# Hive_1_7.net
KiCad netlist of a schematic drawn in EAGLE
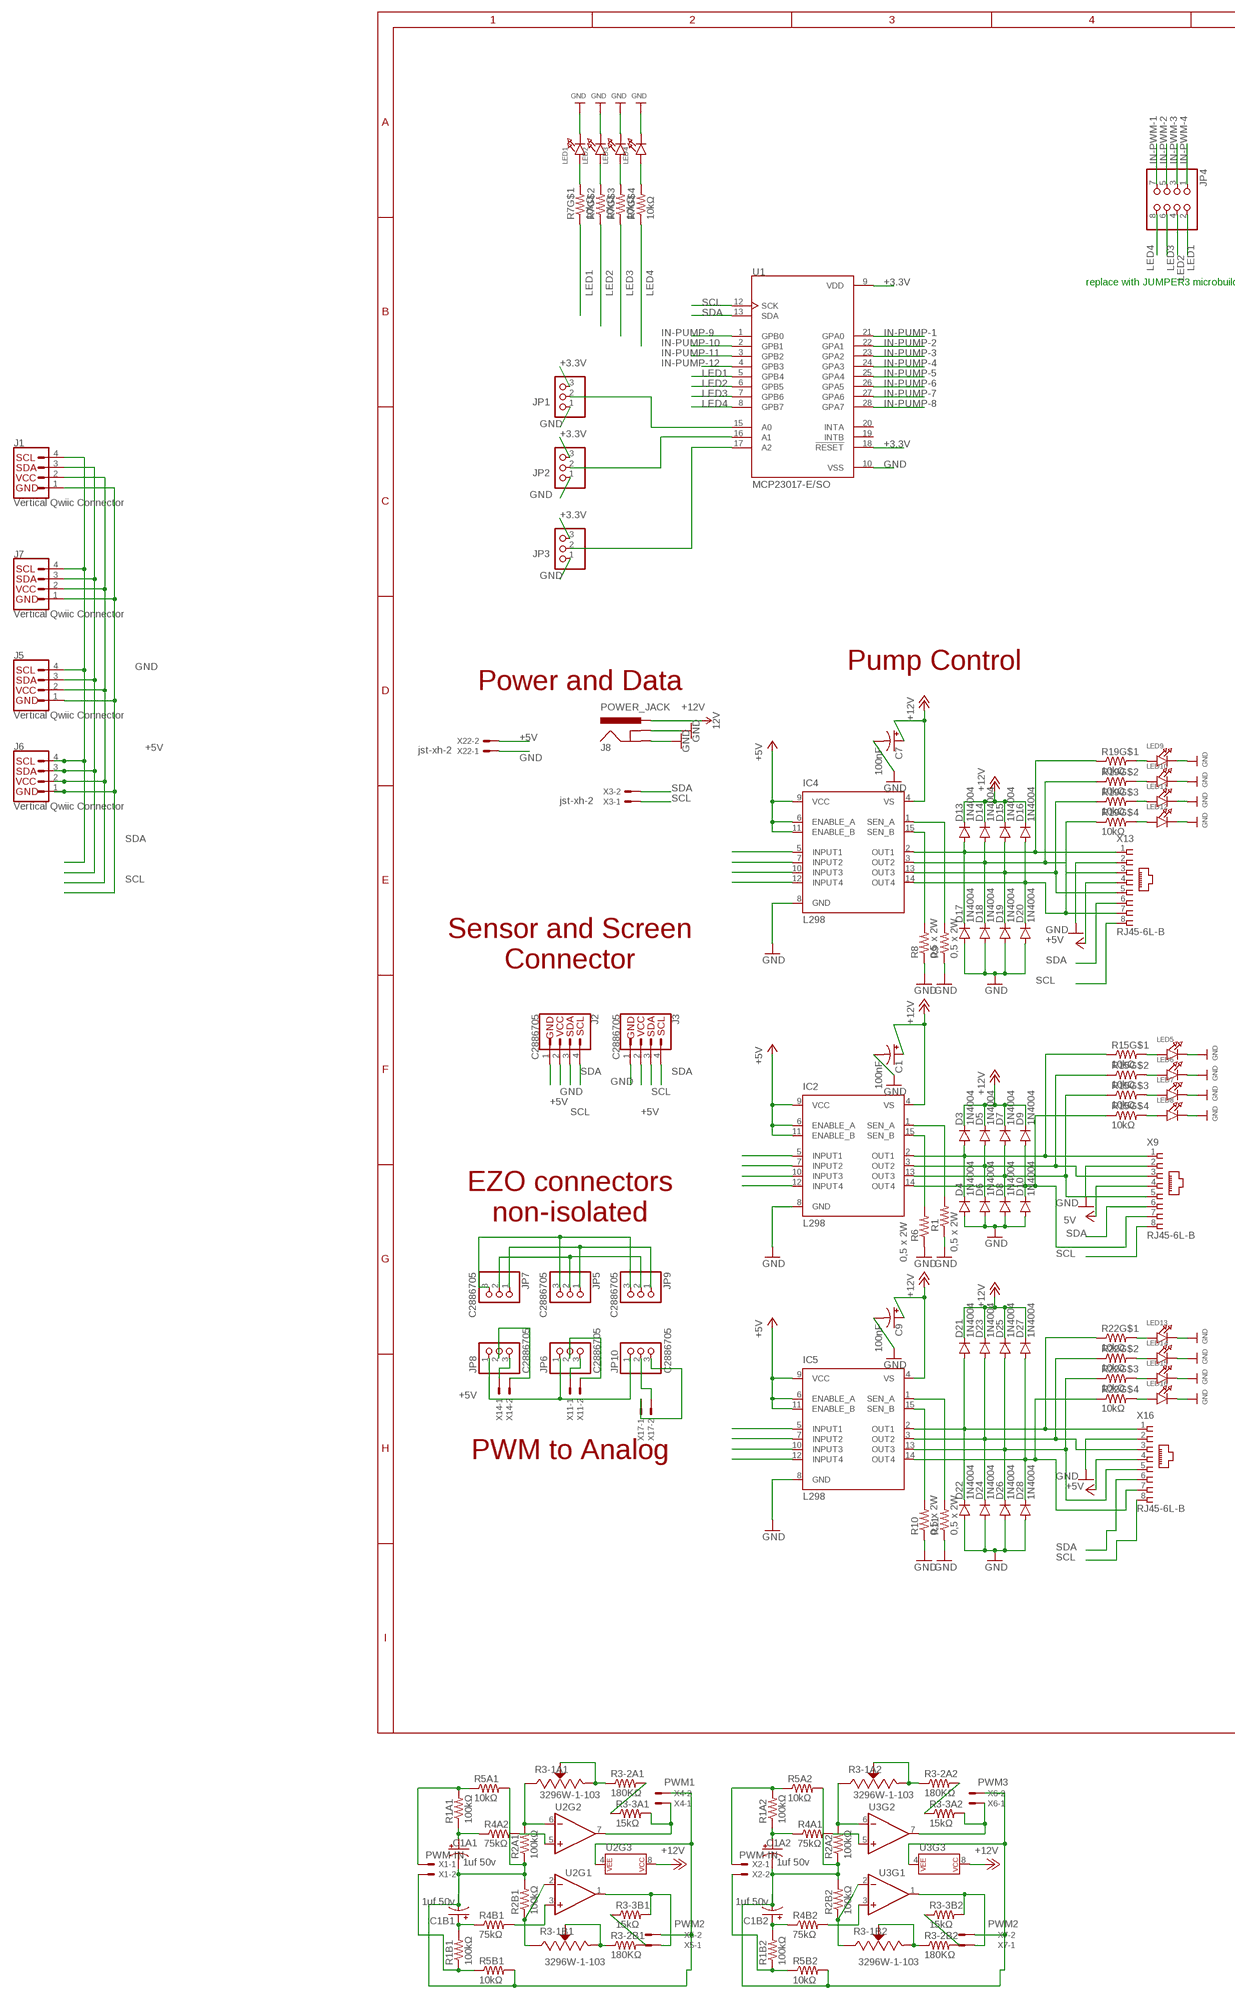
[diagram p0: schematic, sheet 1, part 1 of 2]
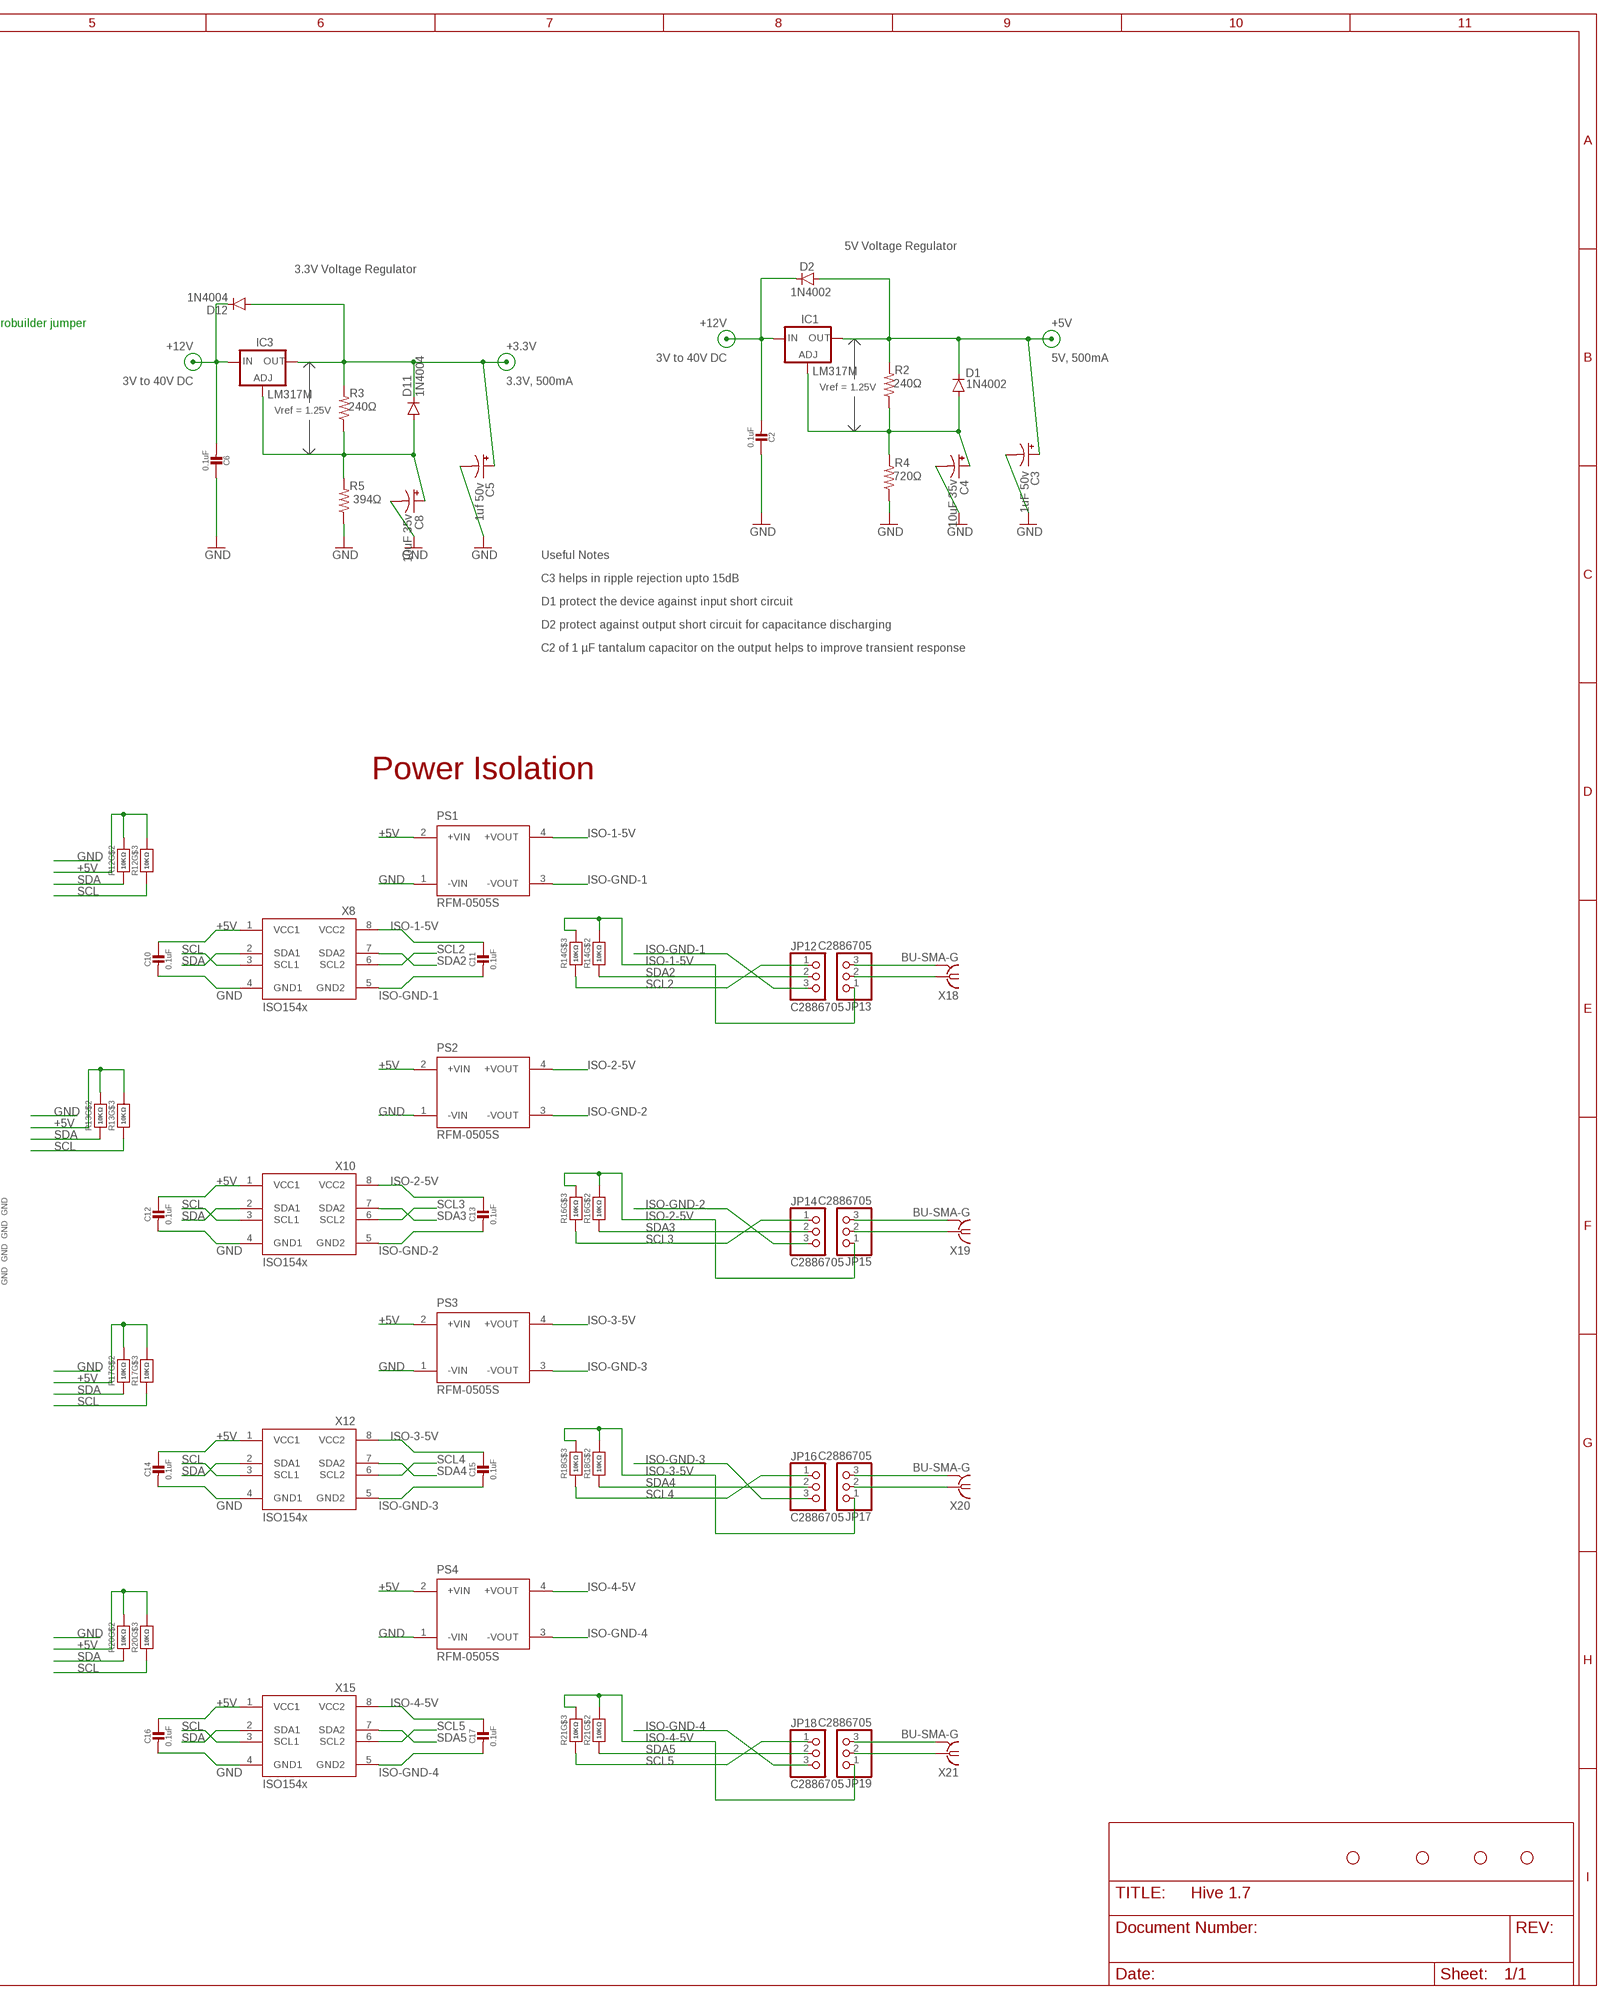
[diagram p1: schematic, sheet 1, part 2 of 2]

(export (version "E")
  (design (tool "Eeschema 10.0.6"))
  (components
    (comp (ref "C1")
      (value "100nF")
      (footprint "eagle-import:UD-4X5,8_NICHICON")
      (libsource (lib "eagle-import") (part "CPOL-USUD-4X5,8"))
    )
    (comp (ref "C1A1")
      (value "1uf 50v")
      (footprint "eagle-import:UD-4X5,8_NICHICON")
      (libsource (lib "eagle-import") (part "CPOL-USUD-4X5,8"))
    )
    (comp (ref "C1A2")
      (value "1uf 50v")
      (footprint "eagle-import:UD-4X5,8_NICHICON")
      (libsource (lib "eagle-import") (part "CPOL-USUD-4X5,8"))
    )
    (comp (ref "C1B1")
      (value "1uf 50v")
      (footprint "eagle-import:UD-4X5,8_NICHICON")
      (libsource (lib "eagle-import") (part "CPOL-USUD-4X5,8"))
    )
    (comp (ref "C1B2")
      (value "1uf 50v")
      (footprint "eagle-import:UD-4X5,8_NICHICON")
      (libsource (lib "eagle-import") (part "CPOL-USUD-4X5,8"))
    )
    (comp (ref "C2")
      (value "0.1uF")
      (footprint "eagle-import:0603-NO")
      (libsource (lib "eagle-import") (part "CAP_CERAMIC0603_NO"))
    )
    (comp (ref "C3")
      (value "1uF 50v")
      (footprint "eagle-import:UD-4X5,8_NICHICON")
      (libsource (lib "eagle-import") (part "CPOL-USUD-4X5,8"))
    )
    (comp (ref "C4")
      (value "10uF 35v")
      (footprint "eagle-import:UD-4X5,8_NICHICON")
      (libsource (lib "eagle-import") (part "CPOL-USUD-4X5,8"))
    )
    (comp (ref "C5")
      (value "1uf 50v")
      (footprint "eagle-import:UD-4X5,8_NICHICON")
      (libsource (lib "eagle-import") (part "CPOL-USUD-4X5,8"))
    )
    (comp (ref "C6")
      (value "0.1uF")
      (footprint "eagle-import:0603-NO")
      (libsource (lib "eagle-import") (part "CAP_CERAMIC0603_NO"))
    )
    (comp (ref "C7")
      (value "100nF")
      (footprint "eagle-import:UD-4X5,8_NICHICON")
      (libsource (lib "eagle-import") (part "CPOL-USUD-4X5,8"))
    )
    (comp (ref "C8")
      (value "10uF 35v")
      (footprint "eagle-import:UD-4X5,8_NICHICON")
      (libsource (lib "eagle-import") (part "CPOL-USUD-4X5,8"))
    )
    (comp (ref "C9")
      (value "100nF")
      (footprint "eagle-import:UD-4X5,8_NICHICON")
      (libsource (lib "eagle-import") (part "CPOL-USUD-4X5,8"))
    )
    (comp (ref "C10")
      (value "0.1uF")
      (footprint "eagle-import:0603-NO")
      (libsource (lib "eagle-import") (part "CAP_CERAMIC0603_NO"))
    )
    (comp (ref "C11")
      (value "0.1uF")
      (footprint "eagle-import:0603-NO")
      (libsource (lib "eagle-import") (part "CAP_CERAMIC0603_NO"))
    )
    (comp (ref "C12")
      (value "0.1uF")
      (footprint "eagle-import:0603-NO")
      (libsource (lib "eagle-import") (part "CAP_CERAMIC0603_NO"))
    )
    (comp (ref "C13")
      (value "0.1uF")
      (footprint "eagle-import:0603-NO")
      (libsource (lib "eagle-import") (part "CAP_CERAMIC0603_NO"))
    )
    (comp (ref "C14")
      (value "0.1uF")
      (footprint "eagle-import:0603-NO")
      (libsource (lib "eagle-import") (part "CAP_CERAMIC0603_NO"))
    )
    (comp (ref "C15")
      (value "0.1uF")
      (footprint "eagle-import:0603-NO")
      (libsource (lib "eagle-import") (part "CAP_CERAMIC0603_NO"))
    )
    (comp (ref "C16")
      (value "0.1uF")
      (footprint "eagle-import:0603-NO")
      (libsource (lib "eagle-import") (part "CAP_CERAMIC0603_NO"))
    )
    (comp (ref "C17")
      (value "0.1uF")
      (footprint "eagle-import:0603-NO")
      (libsource (lib "eagle-import") (part "CAP_CERAMIC0603_NO"))
    )
    (comp (ref "D1")
      (value "1N4002")
      (footprint "eagle-import:DO214BA")
      (libsource (lib "eagle-import") (part "DIODE-DO214BA"))
    )
    (comp (ref "D2")
      (value "1N4002")
      (footprint "eagle-import:DO214BA")
      (libsource (lib "eagle-import") (part "DIODE-DO214BA"))
    )
    (comp (ref "D3")
      (value "1N4004")
      (footprint "eagle-import:DO214BA")
      (libsource (lib "eagle-import") (part "DIODE-DO214BA"))
    )
    (comp (ref "D4")
      (value "1N4004")
      (footprint "eagle-import:DO214BA")
      (libsource (lib "eagle-import") (part "DIODE-DO214BA"))
    )
    (comp (ref "D5")
      (value "1N4004")
      (footprint "eagle-import:DO214BA")
      (libsource (lib "eagle-import") (part "DIODE-DO214BA"))
    )
    (comp (ref "D6")
      (value "1N4004")
      (footprint "eagle-import:DO214BA")
      (libsource (lib "eagle-import") (part "DIODE-DO214BA"))
    )
    (comp (ref "D7")
      (value "1N4004")
      (footprint "eagle-import:DO214BA")
      (libsource (lib "eagle-import") (part "DIODE-DO214BA"))
    )
    (comp (ref "D8")
      (value "1N4004")
      (footprint "eagle-import:DO214BA")
      (libsource (lib "eagle-import") (part "DIODE-DO214BA"))
    )
    (comp (ref "D9")
      (value "1N4004")
      (footprint "eagle-import:DO214BA")
      (libsource (lib "eagle-import") (part "DIODE-DO214BA"))
    )
    (comp (ref "D10")
      (value "1N4004")
      (footprint "eagle-import:DO214BA")
      (libsource (lib "eagle-import") (part "DIODE-DO214BA"))
    )
    (comp (ref "D11")
      (value "1N4004")
      (footprint "eagle-import:DO214BA")
      (libsource (lib "eagle-import") (part "DIODE-DO214BA"))
    )
    (comp (ref "D12")
      (value "1N4004")
      (footprint "eagle-import:DO214BA")
      (libsource (lib "eagle-import") (part "DIODE-DO214BA"))
    )
    (comp (ref "D13")
      (value "1N4004")
      (footprint "eagle-import:DO214BA")
      (libsource (lib "eagle-import") (part "DIODE-DO214BA"))
    )
    (comp (ref "D14")
      (value "1N4004")
      (footprint "eagle-import:DO214BA")
      (libsource (lib "eagle-import") (part "DIODE-DO214BA"))
    )
    (comp (ref "D15")
      (value "1N4004")
      (footprint "eagle-import:DO214BA")
      (libsource (lib "eagle-import") (part "DIODE-DO214BA"))
    )
    (comp (ref "D16")
      (value "1N4004")
      (footprint "eagle-import:DO214BA")
      (libsource (lib "eagle-import") (part "DIODE-DO214BA"))
    )
    (comp (ref "D17")
      (value "1N4004")
      (footprint "eagle-import:DO214BA")
      (libsource (lib "eagle-import") (part "DIODE-DO214BA"))
    )
    (comp (ref "D18")
      (value "1N4004")
      (footprint "eagle-import:DO214BA")
      (libsource (lib "eagle-import") (part "DIODE-DO214BA"))
    )
    (comp (ref "D19")
      (value "1N4004")
      (footprint "eagle-import:DO214BA")
      (libsource (lib "eagle-import") (part "DIODE-DO214BA"))
    )
    (comp (ref "D20")
      (value "1N4004")
      (footprint "eagle-import:DO214BA")
      (libsource (lib "eagle-import") (part "DIODE-DO214BA"))
    )
    (comp (ref "D21")
      (value "1N4004")
      (footprint "eagle-import:DO214BA")
      (libsource (lib "eagle-import") (part "DIODE-DO214BA"))
    )
    (comp (ref "D22")
      (value "1N4004")
      (footprint "eagle-import:DO214BA")
      (libsource (lib "eagle-import") (part "DIODE-DO214BA"))
    )
    (comp (ref "D23")
      (value "1N4004")
      (footprint "eagle-import:DO214BA")
      (libsource (lib "eagle-import") (part "DIODE-DO214BA"))
    )
    (comp (ref "D24")
      (value "1N4004")
      (footprint "eagle-import:DO214BA")
      (libsource (lib "eagle-import") (part "DIODE-DO214BA"))
    )
    (comp (ref "D25")
      (value "1N4004")
      (footprint "eagle-import:DO214BA")
      (libsource (lib "eagle-import") (part "DIODE-DO214BA"))
    )
    (comp (ref "D26")
      (value "1N4004")
      (footprint "eagle-import:DO214BA")
      (libsource (lib "eagle-import") (part "DIODE-DO214BA"))
    )
    (comp (ref "D27")
      (value "1N4004")
      (footprint "eagle-import:DO214BA")
      (libsource (lib "eagle-import") (part "DIODE-DO214BA"))
    )
    (comp (ref "D28")
      (value "1N4004")
      (footprint "eagle-import:DO214BA")
      (libsource (lib "eagle-import") (part "DIODE-DO214BA"))
    )
    (comp (ref "H1")
      (value "STAND-OFF")
      (footprint "eagle-import:STAND-OFF")
      (libsource (lib "eagle-import") (part "STAND-OFF"))
    )
    (comp (ref "H2")
      (value "STAND-OFF")
      (footprint "eagle-import:STAND-OFF")
      (libsource (lib "eagle-import") (part "STAND-OFF"))
    )
    (comp (ref "H3")
      (value "STAND-OFF")
      (footprint "eagle-import:STAND-OFF")
      (libsource (lib "eagle-import") (part "STAND-OFF"))
    )
    (comp (ref "H4")
      (value "STAND-OFF")
      (footprint "eagle-import:STAND-OFF")
      (libsource (lib "eagle-import") (part "STAND-OFF"))
    )
    (comp (ref "IC1")
      (value "LM317MBSTT3")
      (footprint "eagle-import:SOT223")
      (fields (field (name "PARTNUMBER") "LM317M"))
      (libsource (lib "eagle-import") (part "LM317?MBSTT3"))
    )
    (comp (ref "IC2")
      (value "L298")
      (footprint "eagle-import:MULTIWATT-15")
      (fields (field (name "MPN") "L298N"))
      (libsource (lib "eagle-import") (part "L298"))
    )
    (comp (ref "IC3")
      (value "LM317MBSTT3")
      (footprint "eagle-import:SOT223")
      (fields (field (name "PARTNUMBER") "LM317M"))
      (libsource (lib "eagle-import") (part "LM317?MBSTT3"))
    )
    (comp (ref "IC4")
      (value "L298")
      (footprint "eagle-import:MULTIWATT-15")
      (fields (field (name "MPN") "L298N"))
      (libsource (lib "eagle-import") (part "L298"))
    )
    (comp (ref "IC5")
      (value "L298")
      (footprint "eagle-import:MULTIWATT-15")
      (fields (field (name "MPN") "L298N"))
      (libsource (lib "eagle-import") (part "L298"))
    )
    (comp (ref "J1")
      (value "Vertical Qwiic Connector")
      (footprint "eagle-import:JST04_1MM_VERT")
      (libsource (lib "eagle-import") (part "QWIIC_CONNECTOR"))
    )
    (comp (ref "J2")
      (value "C2886705")
      (footprint "eagle-import:1X04")
      (libsource (lib "eagle-import") (part "I2C_STANDARD"))
    )
    (comp (ref "J3")
      (value "C2886705")
      (footprint "eagle-import:1X04")
      (libsource (lib "eagle-import") (part "I2C_STANDARD"))
    )
    (comp (ref "J5")
      (value "Vertical Qwiic Connector")
      (footprint "eagle-import:JST04_1MM_VERT")
      (libsource (lib "eagle-import") (part "QWIIC_CONNECTOR"))
    )
    (comp (ref "J6")
      (value "Vertical Qwiic Connector")
      (footprint "eagle-import:JST04_1MM_VERT")
      (libsource (lib "eagle-import") (part "QWIIC_CONNECTOR"))
    )
    (comp (ref "J7")
      (value "Vertical Qwiic Connector")
      (footprint "eagle-import:JST04_1MM_VERT")
      (libsource (lib "eagle-import") (part "QWIIC_CONNECTOR"))
    )
    (comp (ref "J8")
      (value "POWER_JACK")
      (footprint "eagle-import:POWER_JACK_PTH")
      (libsource (lib "eagle-import") (part "POWER_JACK"))
    )
    (comp (ref "JP1")
      (value "HEADER-1X3ROUND")
      (footprint "eagle-import:1X03_ROUND")
      (libsource (lib "eagle-import") (part "HEADER-1X3ROUND"))
    )
    (comp (ref "JP2")
      (value "HEADER-1X3ROUND")
      (footprint "eagle-import:1X03_ROUND")
      (libsource (lib "eagle-import") (part "HEADER-1X3ROUND"))
    )
    (comp (ref "JP3")
      (value "HEADER-1X3ROUND")
      (footprint "eagle-import:1X03_ROUND")
      (libsource (lib "eagle-import") (part "HEADER-1X3ROUND"))
    )
    (comp (ref "JP4")
      (value "PINHD-2X4")
      (footprint "eagle-import:2X04")
      (libsource (lib "eagle-import") (part "PINHD-2X4"))
    )
    (comp (ref "JP5")
      (value "C2886705")
      (footprint "eagle-import:1X03-CLEANBIG")
      (libsource (lib "eagle-import") (part "PINHD-1X3CB"))
    )
    (comp (ref "JP6")
      (value "C2886705")
      (footprint "eagle-import:1X03-CLEANBIG")
      (libsource (lib "eagle-import") (part "PINHD-1X3CB"))
    )
    (comp (ref "JP7")
      (value "C2886705")
      (footprint "eagle-import:1X03-CLEANBIG")
      (libsource (lib "eagle-import") (part "PINHD-1X3CB"))
    )
    (comp (ref "JP8")
      (value "C2886705")
      (footprint "eagle-import:1X03-CLEANBIG")
      (libsource (lib "eagle-import") (part "PINHD-1X3CB"))
    )
    (comp (ref "JP9")
      (value "C2886705")
      (footprint "eagle-import:1X03-CLEANBIG")
      (libsource (lib "eagle-import") (part "PINHD-1X3CB"))
    )
    (comp (ref "JP10")
      (value "C2886705")
      (footprint "eagle-import:1X03-CLEANBIG")
      (libsource (lib "eagle-import") (part "PINHD-1X3CB"))
    )
    (comp (ref "JP12")
      (value "C2886705")
      (footprint "eagle-import:1X03-CLEANBIG")
      (libsource (lib "eagle-import") (part "PINHD-1X3CB"))
    )
    (comp (ref "JP13")
      (value "C2886705")
      (footprint "eagle-import:1X03-CLEANBIG")
      (libsource (lib "eagle-import") (part "PINHD-1X3CB"))
    )
    (comp (ref "JP14")
      (value "C2886705")
      (footprint "eagle-import:1X03-CLEANBIG")
      (libsource (lib "eagle-import") (part "PINHD-1X3CB"))
    )
    (comp (ref "JP15")
      (value "C2886705")
      (footprint "eagle-import:1X03-CLEANBIG")
      (libsource (lib "eagle-import") (part "PINHD-1X3CB"))
    )
    (comp (ref "JP16")
      (value "C2886705")
      (footprint "eagle-import:1X03-CLEANBIG")
      (libsource (lib "eagle-import") (part "PINHD-1X3CB"))
    )
    (comp (ref "JP17")
      (value "C2886705")
      (footprint "eagle-import:1X03-CLEANBIG")
      (libsource (lib "eagle-import") (part "PINHD-1X3CB"))
    )
    (comp (ref "JP18")
      (value "C2886705")
      (footprint "eagle-import:1X03-CLEANBIG")
      (libsource (lib "eagle-import") (part "PINHD-1X3CB"))
    )
    (comp (ref "JP19")
      (value "C2886705")
      (footprint "eagle-import:1X03-CLEANBIG")
      (libsource (lib "eagle-import") (part "PINHD-1X3CB"))
    )
    (comp (ref "LED1")
      (value "LED0603")
      (footprint "eagle-import:CHIPLED_0603")
      (libsource (lib "eagle-import") (part "LED0603"))
    )
    (comp (ref "LED2")
      (value "LED0603")
      (footprint "eagle-import:CHIPLED_0603")
      (libsource (lib "eagle-import") (part "LED0603"))
    )
    (comp (ref "LED3")
      (value "LED0603")
      (footprint "eagle-import:CHIPLED_0603")
      (libsource (lib "eagle-import") (part "LED0603"))
    )
    (comp (ref "LED4")
      (value "LED0603")
      (footprint "eagle-import:CHIPLED_0603")
      (libsource (lib "eagle-import") (part "LED0603"))
    )
    (comp (ref "LED5")
      (value "LED0603")
      (footprint "eagle-import:CHIPLED_0603")
      (libsource (lib "eagle-import") (part "LED0603"))
    )
    (comp (ref "LED6")
      (value "LED0603")
      (footprint "eagle-import:CHIPLED_0603")
      (libsource (lib "eagle-import") (part "LED0603"))
    )
    (comp (ref "LED7")
      (value "LED0603")
      (footprint "eagle-import:CHIPLED_0603")
      (libsource (lib "eagle-import") (part "LED0603"))
    )
    (comp (ref "LED8")
      (value "LED0603")
      (footprint "eagle-import:CHIPLED_0603")
      (libsource (lib "eagle-import") (part "LED0603"))
    )
    (comp (ref "LED9")
      (value "LED0603")
      (footprint "eagle-import:CHIPLED_0603")
      (libsource (lib "eagle-import") (part "LED0603"))
    )
    (comp (ref "LED10")
      (value "LED0603")
      (footprint "eagle-import:CHIPLED_0603")
      (libsource (lib "eagle-import") (part "LED0603"))
    )
    (comp (ref "LED11")
      (value "LED0603")
      (footprint "eagle-import:CHIPLED_0603")
      (libsource (lib "eagle-import") (part "LED0603"))
    )
    (comp (ref "LED12")
      (value "LED0603")
      (footprint "eagle-import:CHIPLED_0603")
      (libsource (lib "eagle-import") (part "LED0603"))
    )
    (comp (ref "LED13")
      (value "LED0603")
      (footprint "eagle-import:CHIPLED_0603")
      (libsource (lib "eagle-import") (part "LED0603"))
    )
    (comp (ref "LED14")
      (value "LED0603")
      (footprint "eagle-import:CHIPLED_0603")
      (libsource (lib "eagle-import") (part "LED0603"))
    )
    (comp (ref "LED15")
      (value "LED0603")
      (footprint "eagle-import:CHIPLED_0603")
      (libsource (lib "eagle-import") (part "LED0603"))
    )
    (comp (ref "LED16")
      (value "LED0603")
      (footprint "eagle-import:CHIPLED_0603")
      (libsource (lib "eagle-import") (part "LED0603"))
    )
    (comp (ref "PS1")
      (value "RFM-0505S")
      (footprint "eagle-import:CONV_RFM-0505S")
      (fields (field (name "MF") "Recom Power"))
      (libsource (lib "eagle-import") (part "RFM-0505S"))
    )
    (comp (ref "PS2")
      (value "RFM-0505S")
      (footprint "eagle-import:CONV_RFM-0505S")
      (fields (field (name "MF") "Recom Power"))
      (libsource (lib "eagle-import") (part "RFM-0505S"))
    )
    (comp (ref "PS3")
      (value "RFM-0505S")
      (footprint "eagle-import:CONV_RFM-0505S")
      (fields (field (name "MF") "Recom Power"))
      (libsource (lib "eagle-import") (part "RFM-0505S"))
    )
    (comp (ref "PS4")
      (value "RFM-0505S")
      (footprint "eagle-import:CONV_RFM-0505S")
      (fields (field (name "MF") "Recom Power"))
      (libsource (lib "eagle-import") (part "RFM-0505S"))
    )
    (comp (ref "R1")
      (value "0,5 x 2W")
      (footprint "eagle-import:R2512")
      (libsource (lib "eagle-import") (part "R-US_R2512"))
    )
    (comp (ref "R1A1")
      (value "100kΩ")
      (footprint "eagle-import:M1206")
      (libsource (lib "eagle-import") (part "adafruit_420_R-US_M1206"))
    )
    (comp (ref "R1A2")
      (value "100kΩ")
      (footprint "eagle-import:M1206")
      (libsource (lib "eagle-import") (part "adafruit_420_R-US_M1206"))
    )
    (comp (ref "R1B1")
      (value "100kΩ")
      (footprint "eagle-import:M1206")
      (libsource (lib "eagle-import") (part "adafruit_420_R-US_M1206"))
    )
    (comp (ref "R1B2")
      (value "100kΩ")
      (footprint "eagle-import:M1206")
      (libsource (lib "eagle-import") (part "adafruit_420_R-US_M1206"))
    )
    (comp (ref "R2")
      (value "240Ω")
      (footprint "eagle-import:M0805")
      (libsource (lib "eagle-import") (part "resistor_R-US_M0805"))
    )
    (comp (ref "R2A1")
      (value "100kΩ")
      (footprint "eagle-import:M1206")
      (libsource (lib "eagle-import") (part "adafruit_420_R-US_M1206"))
    )
    (comp (ref "R2A2")
      (value "100kΩ")
      (footprint "eagle-import:M1206")
      (libsource (lib "eagle-import") (part "adafruit_420_R-US_M1206"))
    )
    (comp (ref "R2B1")
      (value "100kΩ")
      (footprint "eagle-import:M1206")
      (libsource (lib "eagle-import") (part "adafruit_420_R-US_M1206"))
    )
    (comp (ref "R2B2")
      (value "100kΩ")
      (footprint "eagle-import:M1206")
      (libsource (lib "eagle-import") (part "adafruit_420_R-US_M1206"))
    )
    (comp (ref "R3")
      (value "240Ω")
      (footprint "eagle-import:M0805")
      (libsource (lib "eagle-import") (part "resistor_R-US_M0805"))
    )
    (comp (ref "R3-1A1")
      (value "3296W-1-103")
      (footprint "eagle-import:TRIM_3296W-1-103")
      (fields (field (name "MF") "Bourns"))
      (libsource (lib "eagle-import") (part "3296W-1-103"))
    )
    (comp (ref "R3-1A2")
      (value "3296W-1-103")
      (footprint "eagle-import:TRIM_3296W-1-103")
      (fields (field (name "MF") "Bourns"))
      (libsource (lib "eagle-import") (part "3296W-1-103"))
    )
    (comp (ref "R3-1B1")
      (value "3296W-1-103")
      (footprint "eagle-import:TRIM_3296W-1-103")
      (fields (field (name "MF") "Bourns"))
      (libsource (lib "eagle-import") (part "3296W-1-103"))
    )
    (comp (ref "R3-1B2")
      (value "3296W-1-103")
      (footprint "eagle-import:TRIM_3296W-1-103")
      (fields (field (name "MF") "Bourns"))
      (libsource (lib "eagle-import") (part "3296W-1-103"))
    )
    (comp (ref "R3-2A1")
      (value "180KΩ")
      (footprint "eagle-import:M1206")
      (libsource (lib "eagle-import") (part "adafruit_420_R-US_M1206"))
    )
    (comp (ref "R3-2A2")
      (value "180KΩ")
      (footprint "eagle-import:M1206")
      (libsource (lib "eagle-import") (part "adafruit_420_R-US_M1206"))
    )
    (comp (ref "R3-2B1")
      (value "180KΩ")
      (footprint "eagle-import:M1206")
      (libsource (lib "eagle-import") (part "adafruit_420_R-US_M1206"))
    )
    (comp (ref "R3-2B2")
      (value "180KΩ")
      (footprint "eagle-import:M1206")
      (libsource (lib "eagle-import") (part "adafruit_420_R-US_M1206"))
    )
    (comp (ref "R3-3A1")
      (value "15kΩ")
      (footprint "eagle-import:M1206")
      (libsource (lib "eagle-import") (part "adafruit_420_R-US_M1206"))
    )
    (comp (ref "R3-3A2")
      (value "15kΩ")
      (footprint "eagle-import:M1206")
      (libsource (lib "eagle-import") (part "adafruit_420_R-US_M1206"))
    )
    (comp (ref "R3-3B1")
      (value "15kΩ")
      (footprint "eagle-import:M1206")
      (libsource (lib "eagle-import") (part "adafruit_420_R-US_M1206"))
    )
    (comp (ref "R3-3B2")
      (value "15kΩ")
      (footprint "eagle-import:M1206")
      (libsource (lib "eagle-import") (part "adafruit_420_R-US_M1206"))
    )
    (comp (ref "R4")
      (value "720Ω")
      (footprint "eagle-import:M0805")
      (libsource (lib "eagle-import") (part "resistor_R-US_M0805"))
    )
    (comp (ref "R4A1")
      (value "75kΩ")
      (footprint "eagle-import:M1206")
      (libsource (lib "eagle-import") (part "adafruit_420_R-US_M1206"))
    )
    (comp (ref "R4A2")
      (value "75kΩ")
      (footprint "eagle-import:M1206")
      (libsource (lib "eagle-import") (part "adafruit_420_R-US_M1206"))
    )
    (comp (ref "R4B1")
      (value "75kΩ")
      (footprint "eagle-import:M1206")
      (libsource (lib "eagle-import") (part "adafruit_420_R-US_M1206"))
    )
    (comp (ref "R4B2")
      (value "75kΩ")
      (footprint "eagle-import:M1206")
      (libsource (lib "eagle-import") (part "adafruit_420_R-US_M1206"))
    )
    (comp (ref "R5")
      (value "394Ω")
      (footprint "eagle-import:M0805")
      (libsource (lib "eagle-import") (part "resistor_R-US_M0805"))
    )
    (comp (ref "R5A1")
      (value "10kΩ")
      (footprint "eagle-import:M1206")
      (libsource (lib "eagle-import") (part "adafruit_420_R-US_M1206"))
    )
    (comp (ref "R5A2")
      (value "10kΩ")
      (footprint "eagle-import:M1206")
      (libsource (lib "eagle-import") (part "adafruit_420_R-US_M1206"))
    )
    (comp (ref "R5B1")
      (value "10kΩ")
      (footprint "eagle-import:M1206")
      (libsource (lib "eagle-import") (part "adafruit_420_R-US_M1206"))
    )
    (comp (ref "R5B2")
      (value "10kΩ")
      (footprint "eagle-import:M1206")
      (libsource (lib "eagle-import") (part "adafruit_420_R-US_M1206"))
    )
    (comp (ref "R6")
      (value "0,5 x 2W")
      (footprint "eagle-import:R2512")
      (libsource (lib "eagle-import") (part "R-US_R2512"))
    )
    (comp (ref "R7")
      (value "10kΩ")
      (footprint "eagle-import:RESPACK_4X0603")
      (libsource (lib "eagle-import") (part "RESISTOR_4PACK_US"))
    )
    (comp (ref "R8")
      (value "0,5 x 2W")
      (footprint "eagle-import:R2512")
      (libsource (lib "eagle-import") (part "R-US_R2512"))
    )
    (comp (ref "R9")
      (value "0,5 x 2W")
      (footprint "eagle-import:R2512")
      (libsource (lib "eagle-import") (part "R-US_R2512"))
    )
    (comp (ref "R10")
      (value "0,5 x 2W")
      (footprint "eagle-import:R2512")
      (libsource (lib "eagle-import") (part "R-US_R2512"))
    )
    (comp (ref "R11")
      (value "0,5 x 2W")
      (footprint "eagle-import:R2512")
      (libsource (lib "eagle-import") (part "R-US_R2512"))
    )
    (comp (ref "R12")
      (value "10KΩ")
      (footprint "eagle-import:RESPACK_4X0603")
      (libsource (lib "eagle-import") (part "RESISTOR_4PACK"))
    )
    (comp (ref "R13")
      (value "10KΩ")
      (footprint "eagle-import:RESPACK_4X0603")
      (libsource (lib "eagle-import") (part "RESISTOR_4PACK"))
    )
    (comp (ref "R14")
      (value "10KΩ")
      (footprint "eagle-import:RESPACK_4X0603")
      (libsource (lib "eagle-import") (part "RESISTOR_4PACK"))
    )
    (comp (ref "R15")
      (value "10kΩ")
      (footprint "eagle-import:RESPACK_4X0603")
      (libsource (lib "eagle-import") (part "RESISTOR_4PACK_US"))
    )
    (comp (ref "R16")
      (value "10KΩ")
      (footprint "eagle-import:RESPACK_4X0603")
      (libsource (lib "eagle-import") (part "RESISTOR_4PACK"))
    )
    (comp (ref "R17")
      (value "10KΩ")
      (footprint "eagle-import:RESPACK_4X0603")
      (libsource (lib "eagle-import") (part "RESISTOR_4PACK"))
    )
    (comp (ref "R18")
      (value "10KΩ")
      (footprint "eagle-import:RESPACK_4X0603")
      (libsource (lib "eagle-import") (part "RESISTOR_4PACK"))
    )
    (comp (ref "R19")
      (value "10kΩ")
      (footprint "eagle-import:RESPACK_4X0603")
      (libsource (lib "eagle-import") (part "RESISTOR_4PACK_US"))
    )
    (comp (ref "R20")
      (value "10KΩ")
      (footprint "eagle-import:RESPACK_4X0603")
      (libsource (lib "eagle-import") (part "RESISTOR_4PACK"))
    )
    (comp (ref "R21")
      (value "10KΩ")
      (footprint "eagle-import:RESPACK_4X0603")
      (libsource (lib "eagle-import") (part "RESISTOR_4PACK"))
    )
    (comp (ref "R22")
      (value "10kΩ")
      (footprint "eagle-import:RESPACK_4X0603")
      (libsource (lib "eagle-import") (part "RESISTOR_4PACK_US"))
    )
    (comp (ref "U1")
      (value "MCP23017-E/SO")
      (footprint "eagle-import:SOIC127P1030X265-28N")
      (fields (field (name "MF") "Microchip"))
      (libsource (lib "eagle-import") (part "MCP23017-E/SO"))
    )
    (comp (ref "U2")
      (value "LM358")
      (footprint "eagle-import:SO08")
      (libsource (lib "eagle-import") (part "LM358SO08"))
    )
    (comp (ref "U3")
      (value "LM358")
      (footprint "eagle-import:SO08")
      (libsource (lib "eagle-import") (part "LM358SO08"))
    )
    (comp (ref "X1")
      (value "PWM-IN")
      (footprint "eagle-import:JST-XH-02-PACKAGE-LONG-PAD")
      (libsource (lib "eagle-import") (part "JST-XH-02-PIN-LONG-PAD"))
    )
    (comp (ref "X2")
      (value "PWM-IN")
      (footprint "eagle-import:JST-XH-02-PACKAGE-LONG-PAD")
      (libsource (lib "eagle-import") (part "JST-XH-02-PIN-LONG-PAD"))
    )
    (comp (ref "X3")
      (value "jst-xh-2")
      (footprint "eagle-import:JST-XH-02-PACKAGE-LONG-PAD")
      (libsource (lib "eagle-import") (part "JST-XH-02-PIN-LONG-PAD"))
    )
    (comp (ref "X4")
      (value "PWM1")
      (footprint "eagle-import:JST-XH-02-PACKAGE-LONG-PAD")
      (libsource (lib "eagle-import") (part "JST-XH-02-PIN-LONG-PAD"))
    )
    (comp (ref "X5")
      (value "PWM2")
      (footprint "eagle-import:JST-XH-02-PACKAGE-LONG-PAD")
      (libsource (lib "eagle-import") (part "JST-XH-02-PIN-LONG-PAD"))
    )
    (comp (ref "X6")
      (value "PWM3")
      (footprint "eagle-import:JST-XH-02-PACKAGE-LONG-PAD")
      (libsource (lib "eagle-import") (part "JST-XH-02-PIN-LONG-PAD"))
    )
    (comp (ref "X7")
      (value "PWM2")
      (footprint "eagle-import:JST-XH-02-PACKAGE-LONG-PAD")
      (libsource (lib "eagle-import") (part "JST-XH-02-PIN-LONG-PAD"))
    )
    (comp (ref "X8")
      (value "ISO154X")
      (footprint "eagle-import:SOIC8_150MIL")
      (libsource (lib "eagle-import") (part "ISO154X"))
    )
    (comp (ref "X9")
      (value "RJ45-6L-B")
      (footprint "eagle-import:RJ45-NO-SHIELD")
      (libsource (lib "eagle-import") (part "RJ45-6L-B"))
    )
    (comp (ref "X10")
      (value "ISO154X")
      (footprint "eagle-import:SOIC8_150MIL")
      (libsource (lib "eagle-import") (part "ISO154X"))
    )
    (comp (ref "X11")
      (value "jst-xh-2")
      (footprint "eagle-import:JST-XH-02-PACKAGE-LONG-PAD")
      (libsource (lib "eagle-import") (part "JST-XH-02-PIN-LONG-PAD"))
    )
    (comp (ref "X12")
      (value "ISO154X")
      (footprint "eagle-import:SOIC8_150MIL")
      (libsource (lib "eagle-import") (part "ISO154X"))
    )
    (comp (ref "X13")
      (value "RJ45-6L-B")
      (footprint "eagle-import:RJ45-NO-SHIELD")
      (libsource (lib "eagle-import") (part "RJ45-6L-B"))
    )
    (comp (ref "X14")
      (value "jst-xh-2")
      (footprint "eagle-import:JST-XH-02-PACKAGE-LONG-PAD")
      (libsource (lib "eagle-import") (part "JST-XH-02-PIN-LONG-PAD"))
    )
    (comp (ref "X15")
      (value "ISO154X")
      (footprint "eagle-import:SOIC8_150MIL")
      (libsource (lib "eagle-import") (part "ISO154X"))
    )
    (comp (ref "X16")
      (value "RJ45-6L-B")
      (footprint "eagle-import:RJ45-NO-SHIELD")
      (libsource (lib "eagle-import") (part "RJ45-6L-B"))
    )
    (comp (ref "X17")
      (value "jst-xh-2")
      (footprint "eagle-import:JST-XH-02-PACKAGE-LONG-PAD")
      (libsource (lib "eagle-import") (part "JST-XH-02-PIN-LONG-PAD"))
    )
    (comp (ref "X18")
      (value "BU-SMA-G")
      (footprint "eagle-import:BU-SMA-G")
      (libsource (lib "eagle-import") (part "BU-SMA-G"))
    )
    (comp (ref "X19")
      (value "BU-SMA-G")
      (footprint "eagle-import:BU-SMA-G")
      (libsource (lib "eagle-import") (part "BU-SMA-G"))
    )
    (comp (ref "X20")
      (value "BU-SMA-G")
      (footprint "eagle-import:BU-SMA-G")
      (libsource (lib "eagle-import") (part "BU-SMA-G"))
    )
    (comp (ref "X21")
      (value "BU-SMA-G")
      (footprint "eagle-import:BU-SMA-G")
      (libsource (lib "eagle-import") (part "BU-SMA-G"))
    )
    (comp (ref "X22")
      (value "jst-xh-2")
      (footprint "eagle-import:JST-XH-02-PACKAGE-LONG-PAD")
      (libsource (lib "eagle-import") (part "JST-XH-02-PIN-LONG-PAD"))
    )
  )
  (nets
    (net (code "1") (name "+3V3") (class "Default")
      (node (ref "C10") (pin "1") (pinfunction "1_1") (pintype "passive"))
      (node (ref "C12") (pin "1") (pinfunction "1_1") (pintype "passive"))
      (node (ref "C14") (pin "1") (pinfunction "1_1") (pintype "passive"))
      (node (ref "C16") (pin "1") (pinfunction "1_1") (pintype "passive"))
      (node (ref "C3") (pin "+") (pinfunction "+_+") (pintype "passive"))
      (node (ref "D1") (pin "C") (pinfunction "C_C") (pintype "passive"))
      (node (ref "D2") (pin "A") (pinfunction "A_A") (pintype "passive"))
      (node (ref "IC1") (pin "4") (pinfunction "OUT_4") (pintype "passive"))
      (node (ref "IC2") (pin "11") (pinfunction "ENABLE_B_11") (pintype "input"))
      (node (ref "IC2") (pin "6") (pinfunction "ENABLE_A_6") (pintype "input"))
      (node (ref "IC2") (pin "9") (pinfunction "VCC_9") (pintype "power_in"))
      (node (ref "IC4") (pin "11") (pinfunction "ENABLE_B_11") (pintype "input"))
      (node (ref "IC4") (pin "6") (pinfunction "ENABLE_A_6") (pintype "input"))
      (node (ref "IC4") (pin "9") (pinfunction "VCC_9") (pintype "power_in"))
      (node (ref "IC5") (pin "11") (pinfunction "ENABLE_B_11") (pintype "input"))
      (node (ref "IC5") (pin "6") (pinfunction "ENABLE_A_6") (pintype "input"))
      (node (ref "IC5") (pin "9") (pinfunction "VCC_9") (pintype "power_in"))
      (node (ref "J1") (pin "3") (pinfunction "3_3") (pintype "passive"))
      (node (ref "J2") (pin "1") (pinfunction "1_1") (pintype "power_in"))
      (node (ref "J3") (pin "2") (pinfunction "2_2") (pintype "power_in"))
      (node (ref "J5") (pin "3") (pinfunction "3_3") (pintype "passive"))
      (node (ref "J6") (pin "3") (pinfunction "3_3") (pintype "passive"))
      (node (ref "J7") (pin "3") (pinfunction "3_3") (pintype "passive"))
      (node (ref "JP10") (pin "1") (pinfunction "1_1") (pintype "passive"))
      (node (ref "JP6") (pin "1") (pinfunction "1_1") (pintype "passive"))
      (node (ref "JP8") (pin "1") (pinfunction "1_1") (pintype "passive"))
      (node (ref "PS1") (pin "2") (pinfunction "+VIN_2") (pintype "input"))
      (node (ref "PS2") (pin "2") (pinfunction "+VIN_2") (pintype "input"))
      (node (ref "PS3") (pin "2") (pinfunction "+VIN_2") (pintype "input"))
      (node (ref "PS4") (pin "2") (pinfunction "+VIN_2") (pintype "input"))
      (node (ref "R12") (pin "6") (pinfunction "2_6") (pintype "passive"))
      (node (ref "R12") (pin "7") (pinfunction "2_7") (pintype "passive"))
      (node (ref "R13") (pin "6") (pinfunction "2_6") (pintype "passive"))
      (node (ref "R13") (pin "7") (pinfunction "2_7") (pintype "passive"))
      (node (ref "R17") (pin "6") (pinfunction "2_6") (pintype "passive"))
      (node (ref "R17") (pin "7") (pinfunction "2_7") (pintype "passive"))
      (node (ref "R2") (pin "2") (pinfunction "2_2") (pintype "passive"))
      (node (ref "R20") (pin "6") (pinfunction "2_6") (pintype "passive"))
      (node (ref "R20") (pin "7") (pinfunction "2_7") (pintype "passive"))
      (node (ref "X10") (pin "1") (pinfunction "VCC1_1") (pintype "power_in"))
      (node (ref "X12") (pin "1") (pinfunction "VCC1_1") (pintype "power_in"))
      (node (ref "X13") (pin "4") (pinfunction "4_4") (pintype "passive"))
      (node (ref "X15") (pin "1") (pinfunction "VCC1_1") (pintype "power_in"))
      (node (ref "X16") (pin "4") (pinfunction "4_4") (pintype "passive"))
      (node (ref "X22") (pin "2") (pinfunction "S_2") (pintype "passive"))
      (node (ref "X8") (pin "1") (pinfunction "VCC1_1") (pintype "power_in"))
      (node (ref "X9") (pin "4") (pinfunction "4_4") (pintype "passive"))
    )
    (net (code "2") (name "+12V") (class "Default")
      (node (ref "C1") (pin "+") (pinfunction "+_+") (pintype "passive"))
      (node (ref "C2") (pin "2") (pinfunction "2_2") (pintype "passive"))
      (node (ref "C6") (pin "2") (pinfunction "2_2") (pintype "passive"))
      (node (ref "C7") (pin "+") (pinfunction "+_+") (pintype "passive"))
      (node (ref "C9") (pin "+") (pinfunction "+_+") (pintype "passive"))
      (node (ref "D12") (pin "C") (pinfunction "C_C") (pintype "passive"))
      (node (ref "D13") (pin "C") (pinfunction "C_C") (pintype "passive"))
      (node (ref "D14") (pin "C") (pinfunction "C_C") (pintype "passive"))
      (node (ref "D15") (pin "C") (pinfunction "C_C") (pintype "passive"))
      (node (ref "D16") (pin "C") (pinfunction "C_C") (pintype "passive"))
      (node (ref "D2") (pin "C") (pinfunction "C_C") (pintype "passive"))
      (node (ref "D21") (pin "C") (pinfunction "C_C") (pintype "passive"))
      (node (ref "D23") (pin "C") (pinfunction "C_C") (pintype "passive"))
      (node (ref "D25") (pin "C") (pinfunction "C_C") (pintype "passive"))
      (node (ref "D27") (pin "C") (pinfunction "C_C") (pintype "passive"))
      (node (ref "D3") (pin "C") (pinfunction "C_C") (pintype "passive"))
      (node (ref "D5") (pin "C") (pinfunction "C_C") (pintype "passive"))
      (node (ref "D7") (pin "C") (pinfunction "C_C") (pintype "passive"))
      (node (ref "D9") (pin "C") (pinfunction "C_C") (pintype "passive"))
      (node (ref "IC1") (pin "3") (pinfunction "IN_3") (pintype "input"))
      (node (ref "IC2") (pin "4") (pinfunction "VS_4") (pintype "power_in"))
      (node (ref "IC3") (pin "3") (pinfunction "IN_3") (pintype "input"))
      (node (ref "IC4") (pin "4") (pinfunction "VS_4") (pintype "power_in"))
      (node (ref "IC5") (pin "4") (pinfunction "VS_4") (pintype "power_in"))
      (node (ref "J8") (pin "PWR") (pinfunction "PWR_PWR") (pintype "bidirectional"))
      (node (ref "U2") (pin "8") (pinfunction "P$V+_8") (pintype "bidirectional"))
      (node (ref "U3") (pin "8") (pinfunction "P$V+_8") (pintype "bidirectional"))
    )
    (net (code "3") (name "/+3.3V") (class "Default")
      (node (ref "C5") (pin "+") (pinfunction "+_+") (pintype "passive"))
      (node (ref "D11") (pin "C") (pinfunction "C_C") (pintype "passive"))
      (node (ref "D12") (pin "A") (pinfunction "A_A") (pintype "passive"))
      (node (ref "IC3") (pin "4") (pinfunction "OUT_4") (pintype "passive"))
      (node (ref "JP1") (pin "3") (pinfunction "3_3") (pintype "passive"))
      (node (ref "JP2") (pin "3") (pinfunction "3_3") (pintype "passive"))
      (node (ref "JP3") (pin "3") (pinfunction "3_3") (pintype "passive"))
      (node (ref "R3") (pin "2") (pinfunction "2_2") (pintype "passive"))
      (node (ref "U1") (pin "18") (pinfunction "~{RESET}_18") (pintype "output"))
      (node (ref "U1") (pin "9") (pinfunction "VDD_9") (pintype "power_in"))
    )
    (net (code "4") (name "/IN-PUMP-1") (class "Default")
      (node (ref "IC2") (pin "5") (pinfunction "INPUT1_5") (pintype "input"))
      (node (ref "U1") (pin "21") (pinfunction "GPA0_21") (pintype "bidirectional"))
    )
    (net (code "5") (name "/IN-PUMP-2") (class "Default")
      (node (ref "IC2") (pin "7") (pinfunction "INPUT2_7") (pintype "input"))
      (node (ref "U1") (pin "22") (pinfunction "GPA1_22") (pintype "bidirectional"))
    )
    (net (code "6") (name "/IN-PUMP-3") (class "Default")
      (node (ref "IC2") (pin "10") (pinfunction "INPUT3_10") (pintype "input"))
      (node (ref "U1") (pin "23") (pinfunction "GPA2_23") (pintype "bidirectional"))
    )
    (net (code "7") (name "/IN-PUMP-4") (class "Default")
      (node (ref "IC2") (pin "12") (pinfunction "INPUT4_12") (pintype "input"))
      (node (ref "U1") (pin "24") (pinfunction "GPA3_24") (pintype "bidirectional"))
    )
    (net (code "8") (name "/IN-PUMP-5") (class "Default")
      (node (ref "IC4") (pin "5") (pinfunction "INPUT1_5") (pintype "input"))
      (node (ref "U1") (pin "25") (pinfunction "GPA4_25") (pintype "bidirectional"))
    )
    (net (code "9") (name "/IN-PUMP-6") (class "Default")
      (node (ref "IC4") (pin "7") (pinfunction "INPUT2_7") (pintype "input"))
      (node (ref "U1") (pin "26") (pinfunction "GPA5_26") (pintype "bidirectional"))
    )
    (net (code "10") (name "/IN-PUMP-7") (class "Default")
      (node (ref "IC4") (pin "10") (pinfunction "INPUT3_10") (pintype "input"))
      (node (ref "U1") (pin "27") (pinfunction "GPA6_27") (pintype "bidirectional"))
    )
    (net (code "11") (name "/IN-PUMP-8") (class "Default")
      (node (ref "IC4") (pin "12") (pinfunction "INPUT4_12") (pintype "input"))
      (node (ref "U1") (pin "28") (pinfunction "GPA7_28") (pintype "bidirectional"))
    )
    (net (code "12") (name "/IN-PUMP-9") (class "Default")
      (node (ref "IC5") (pin "5") (pinfunction "INPUT1_5") (pintype "input"))
      (node (ref "U1") (pin "1") (pinfunction "GPB0_1") (pintype "bidirectional"))
    )
    (net (code "13") (name "/IN-PUMP-10") (class "Default")
      (node (ref "IC5") (pin "7") (pinfunction "INPUT2_7") (pintype "input"))
      (node (ref "U1") (pin "2") (pinfunction "GPB1_2") (pintype "bidirectional"))
    )
    (net (code "14") (name "/IN-PUMP-11") (class "Default")
      (node (ref "IC5") (pin "10") (pinfunction "INPUT3_10") (pintype "input"))
      (node (ref "U1") (pin "3") (pinfunction "GPB2_3") (pintype "bidirectional"))
    )
    (net (code "15") (name "/IN-PUMP-12") (class "Default")
      (node (ref "IC5") (pin "12") (pinfunction "INPUT4_12") (pintype "input"))
      (node (ref "U1") (pin "4") (pinfunction "GPB3_4") (pintype "bidirectional"))
    )
    (net (code "16") (name "/IN-PWM-1") (class "Default")
      (node (ref "JP4") (pin "7") (pinfunction "7_7") (pintype "passive"))
      (node (ref "R1A1") (pin "2") (pinfunction "2_2") (pintype "passive"))
      (node (ref "R5A1") (pin "1") (pinfunction "1_1") (pintype "passive"))
      (node (ref "X1") (pin "1") (pinfunction "S_1") (pintype "passive"))
    )
    (net (code "17") (name "/IN-PWM-2") (class "Default")
      (node (ref "JP4") (pin "5") (pinfunction "5_5") (pintype "passive"))
      (node (ref "R1B1") (pin "1") (pinfunction "1_1") (pintype "passive"))
      (node (ref "R5B1") (pin "1") (pinfunction "1_1") (pintype "passive"))
      (node (ref "X1") (pin "2") (pinfunction "S_2") (pintype "passive"))
    )
    (net (code "18") (name "/IN-PWM-3") (class "Default")
      (node (ref "JP4") (pin "3") (pinfunction "3_3") (pintype "passive"))
      (node (ref "R1A2") (pin "2") (pinfunction "2_2") (pintype "passive"))
      (node (ref "R5A2") (pin "1") (pinfunction "1_1") (pintype "passive"))
      (node (ref "X2") (pin "1") (pinfunction "S_1") (pintype "passive"))
    )
    (net (code "19") (name "/IN-PWM-4") (class "Default")
      (node (ref "JP4") (pin "1") (pinfunction "1_1") (pintype "passive"))
      (node (ref "R1B2") (pin "1") (pinfunction "1_1") (pintype "passive"))
      (node (ref "R5B2") (pin "1") (pinfunction "1_1") (pintype "passive"))
      (node (ref "X2") (pin "2") (pinfunction "S_2") (pintype "passive"))
    )
    (net (code "20") (name "/ISO-1-5V") (class "Default")
      (node (ref "C11") (pin "1") (pinfunction "1_1") (pintype "passive"))
      (node (ref "JP13") (pin "1") (pinfunction "1_1") (pintype "passive"))
      (node (ref "PS1") (pin "4") (pinfunction "+VOUT_4") (pintype "output"))
      (node (ref "R14") (pin "6") (pinfunction "2_6") (pintype "passive"))
      (node (ref "R14") (pin "7") (pinfunction "2_7") (pintype "passive"))
      (node (ref "X8") (pin "8") (pinfunction "VCC2_8") (pintype "power_in"))
    )
    (net (code "21") (name "/ISO-2-5V") (class "Default")
      (node (ref "C13") (pin "1") (pinfunction "1_1") (pintype "passive"))
      (node (ref "JP15") (pin "1") (pinfunction "1_1") (pintype "passive"))
      (node (ref "PS2") (pin "4") (pinfunction "+VOUT_4") (pintype "output"))
      (node (ref "R16") (pin "6") (pinfunction "2_6") (pintype "passive"))
      (node (ref "R16") (pin "7") (pinfunction "2_7") (pintype "passive"))
      (node (ref "X10") (pin "8") (pinfunction "VCC2_8") (pintype "power_in"))
    )
    (net (code "22") (name "/ISO-3-5V") (class "Default")
      (node (ref "C15") (pin "1") (pinfunction "1_1") (pintype "passive"))
      (node (ref "JP17") (pin "1") (pinfunction "1_1") (pintype "passive"))
      (node (ref "PS3") (pin "4") (pinfunction "+VOUT_4") (pintype "output"))
      (node (ref "R18") (pin "6") (pinfunction "2_6") (pintype "passive"))
      (node (ref "R18") (pin "7") (pinfunction "2_7") (pintype "passive"))
      (node (ref "X12") (pin "8") (pinfunction "VCC2_8") (pintype "power_in"))
    )
    (net (code "23") (name "/ISO-4-5V") (class "Default")
      (node (ref "C17") (pin "1") (pinfunction "1_1") (pintype "passive"))
      (node (ref "JP19") (pin "1") (pinfunction "1_1") (pintype "passive"))
      (node (ref "PS4") (pin "4") (pinfunction "+VOUT_4") (pintype "output"))
      (node (ref "R21") (pin "6") (pinfunction "2_6") (pintype "passive"))
      (node (ref "R21") (pin "7") (pinfunction "2_7") (pintype "passive"))
      (node (ref "X15") (pin "8") (pinfunction "VCC2_8") (pintype "power_in"))
    )
    (net (code "24") (name "/ISO-GND-1") (class "Default")
      (node (ref "C11") (pin "2") (pinfunction "2_2") (pintype "passive"))
      (node (ref "JP12") (pin "3") (pinfunction "3_3") (pintype "passive"))
      (node (ref "PS1") (pin "3") (pinfunction "-VOUT_3") (pintype "output"))
      (node (ref "X8") (pin "5") (pinfunction "GND2_5") (pintype "power_in"))
    )
    (net (code "25") (name "/ISO-GND-2") (class "Default")
      (node (ref "C13") (pin "2") (pinfunction "2_2") (pintype "passive"))
      (node (ref "JP14") (pin "3") (pinfunction "3_3") (pintype "passive"))
      (node (ref "PS2") (pin "3") (pinfunction "-VOUT_3") (pintype "output"))
      (node (ref "X10") (pin "5") (pinfunction "GND2_5") (pintype "power_in"))
    )
    (net (code "26") (name "/ISO-GND-3") (class "Default")
      (node (ref "C15") (pin "2") (pinfunction "2_2") (pintype "passive"))
      (node (ref "JP16") (pin "3") (pinfunction "3_3") (pintype "passive"))
      (node (ref "PS3") (pin "3") (pinfunction "-VOUT_3") (pintype "output"))
      (node (ref "X12") (pin "5") (pinfunction "GND2_5") (pintype "power_in"))
    )
    (net (code "27") (name "/ISO-GND-4") (class "Default")
      (node (ref "C17") (pin "2") (pinfunction "2_2") (pintype "passive"))
      (node (ref "JP18") (pin "3") (pinfunction "3_3") (pintype "passive"))
      (node (ref "PS4") (pin "3") (pinfunction "-VOUT_3") (pintype "output"))
      (node (ref "X15") (pin "5") (pinfunction "GND2_5") (pintype "power_in"))
    )
    (net (code "28") (name "/LED1") (class "Default")
      (node (ref "JP4") (pin "2") (pinfunction "2_2") (pintype "passive"))
      (node (ref "R7") (pin "1") (pinfunction "1_1") (pintype "passive"))
      (node (ref "U1") (pin "5") (pinfunction "GPB4_5") (pintype "bidirectional"))
    )
    (net (code "29") (name "/LED2") (class "Default")
      (node (ref "JP4") (pin "4") (pinfunction "4_4") (pintype "passive"))
      (node (ref "R7") (pin "2") (pinfunction "1_2") (pintype "passive"))
      (node (ref "U1") (pin "6") (pinfunction "GPB5_6") (pintype "bidirectional"))
    )
    (net (code "30") (name "/LED3") (class "Default")
      (node (ref "JP4") (pin "6") (pinfunction "6_6") (pintype "passive"))
      (node (ref "R7") (pin "3") (pinfunction "1_3") (pintype "passive"))
      (node (ref "U1") (pin "7") (pinfunction "GPB6_7") (pintype "bidirectional"))
    )
    (net (code "31") (name "/LED4") (class "Default")
      (node (ref "JP4") (pin "8") (pinfunction "8_8") (pintype "passive"))
      (node (ref "R7") (pin "4") (pinfunction "1_4") (pintype "passive"))
      (node (ref "U1") (pin "8") (pinfunction "GPB7_8") (pintype "bidirectional"))
    )
    (net (code "32") (name "/SCL") (class "Default")
      (node (ref "J1") (pin "1") (pinfunction "1_1") (pintype "power_in"))
      (node (ref "J2") (pin "3") (pinfunction "3_3") (pintype "passive"))
      (node (ref "J3") (pin "3") (pinfunction "3_3") (pintype "passive"))
      (node (ref "J5") (pin "1") (pinfunction "1_1") (pintype "power_in"))
      (node (ref "J6") (pin "1") (pinfunction "1_1") (pintype "power_in"))
      (node (ref "J7") (pin "1") (pinfunction "1_1") (pintype "power_in"))
      (node (ref "JP5") (pin "1") (pinfunction "1_1") (pintype "passive"))
      (node (ref "JP7") (pin "1") (pinfunction "1_1") (pintype "passive"))
      (node (ref "JP9") (pin "1") (pinfunction "1_1") (pintype "passive"))
      (node (ref "R12") (pin "3") (pinfunction "1_3") (pintype "passive"))
      (node (ref "R13") (pin "3") (pinfunction "1_3") (pintype "passive"))
      (node (ref "R17") (pin "3") (pinfunction "1_3") (pintype "passive"))
      (node (ref "R20") (pin "3") (pinfunction "1_3") (pintype "passive"))
      (node (ref "U1") (pin "12") (pinfunction "SCK_12") (pintype "input"))
      (node (ref "X10") (pin "3") (pinfunction "SCL1_3") (pintype "bidirectional"))
      (node (ref "X12") (pin "3") (pinfunction "SCL1_3") (pintype "bidirectional"))
      (node (ref "X13") (pin "8") (pinfunction "8_8") (pintype "passive"))
      (node (ref "X15") (pin "3") (pinfunction "SCL1_3") (pintype "bidirectional"))
      (node (ref "X16") (pin "8") (pinfunction "8_8") (pintype "passive"))
      (node (ref "X3") (pin "1") (pinfunction "S_1") (pintype "passive"))
      (node (ref "X8") (pin "3") (pinfunction "SCL1_3") (pintype "bidirectional"))
      (node (ref "X9") (pin "8") (pinfunction "8_8") (pintype "passive"))
    )
    (net (code "33") (name "/SCL2") (class "Default")
      (node (ref "JP12") (pin "1") (pinfunction "1_1") (pintype "passive"))
      (node (ref "R14") (pin "3") (pinfunction "1_3") (pintype "passive"))
      (node (ref "X8") (pin "6") (pinfunction "SCL2_6") (pintype "bidirectional"))
    )
    (net (code "34") (name "/SCL3") (class "Default")
      (node (ref "JP14") (pin "1") (pinfunction "1_1") (pintype "passive"))
      (node (ref "R16") (pin "3") (pinfunction "1_3") (pintype "passive"))
      (node (ref "X10") (pin "6") (pinfunction "SCL2_6") (pintype "bidirectional"))
    )
    (net (code "35") (name "/SCL4") (class "Default")
      (node (ref "JP16") (pin "1") (pinfunction "1_1") (pintype "passive"))
      (node (ref "R18") (pin "3") (pinfunction "1_3") (pintype "passive"))
      (node (ref "X12") (pin "6") (pinfunction "SCL2_6") (pintype "bidirectional"))
    )
    (net (code "36") (name "/SCL5") (class "Default")
      (node (ref "JP18") (pin "1") (pinfunction "1_1") (pintype "passive"))
      (node (ref "R21") (pin "3") (pinfunction "1_3") (pintype "passive"))
      (node (ref "X15") (pin "6") (pinfunction "SCL2_6") (pintype "bidirectional"))
    )
    (net (code "37") (name "/SDA") (class "Default")
      (node (ref "J1") (pin "2") (pinfunction "2_2") (pintype "power_in"))
      (node (ref "J2") (pin "4") (pinfunction "4_4") (pintype "passive"))
      (node (ref "J3") (pin "4") (pinfunction "4_4") (pintype "passive"))
      (node (ref "J5") (pin "2") (pinfunction "2_2") (pintype "power_in"))
      (node (ref "J6") (pin "2") (pinfunction "2_2") (pintype "power_in"))
      (node (ref "J7") (pin "2") (pinfunction "2_2") (pintype "power_in"))
      (node (ref "JP5") (pin "2") (pinfunction "2_2") (pintype "passive"))
      (node (ref "JP7") (pin "2") (pinfunction "2_2") (pintype "passive"))
      (node (ref "JP9") (pin "2") (pinfunction "2_2") (pintype "passive"))
      (node (ref "R12") (pin "2") (pinfunction "1_2") (pintype "passive"))
      (node (ref "R13") (pin "2") (pinfunction "1_2") (pintype "passive"))
      (node (ref "R17") (pin "2") (pinfunction "1_2") (pintype "passive"))
      (node (ref "R20") (pin "2") (pinfunction "1_2") (pintype "passive"))
      (node (ref "U1") (pin "13") (pinfunction "SDA_13") (pintype "bidirectional"))
      (node (ref "X10") (pin "2") (pinfunction "SDA1_2") (pintype "bidirectional"))
      (node (ref "X12") (pin "2") (pinfunction "SDA1_2") (pintype "bidirectional"))
      (node (ref "X13") (pin "6") (pinfunction "6_6") (pintype "passive"))
      (node (ref "X15") (pin "2") (pinfunction "SDA1_2") (pintype "bidirectional"))
      (node (ref "X16") (pin "6") (pinfunction "6_6") (pintype "passive"))
      (node (ref "X3") (pin "2") (pinfunction "S_2") (pintype "passive"))
      (node (ref "X8") (pin "2") (pinfunction "SDA1_2") (pintype "bidirectional"))
      (node (ref "X9") (pin "6") (pinfunction "6_6") (pintype "passive"))
    )
    (net (code "38") (name "/SDA2") (class "Default")
      (node (ref "JP12") (pin "2") (pinfunction "2_2") (pintype "passive"))
      (node (ref "R14") (pin "2") (pinfunction "1_2") (pintype "passive"))
      (node (ref "X8") (pin "7") (pinfunction "SDA2_7") (pintype "bidirectional"))
    )
    (net (code "39") (name "/SDA3") (class "Default")
      (node (ref "JP14") (pin "2") (pinfunction "2_2") (pintype "passive"))
      (node (ref "R16") (pin "2") (pinfunction "1_2") (pintype "passive"))
      (node (ref "X10") (pin "7") (pinfunction "SDA2_7") (pintype "bidirectional"))
    )
    (net (code "40") (name "/SDA4") (class "Default")
      (node (ref "JP16") (pin "2") (pinfunction "2_2") (pintype "passive"))
      (node (ref "R18") (pin "2") (pinfunction "1_2") (pintype "passive"))
      (node (ref "X12") (pin "7") (pinfunction "SDA2_7") (pintype "bidirectional"))
    )
    (net (code "41") (name "/SDA5") (class "Default")
      (node (ref "JP18") (pin "2") (pinfunction "2_2") (pintype "passive"))
      (node (ref "R21") (pin "2") (pinfunction "1_2") (pintype "passive"))
      (node (ref "X15") (pin "7") (pinfunction "SDA2_7") (pintype "bidirectional"))
    )
    (net (code "42") (name "GND") (class "Default")
      (node (ref "C1") (pin "-") (pinfunction "-_-") (pintype "passive"))
      (node (ref "C10") (pin "2") (pinfunction "2_2") (pintype "passive"))
      (node (ref "C12") (pin "2") (pinfunction "2_2") (pintype "passive"))
      (node (ref "C14") (pin "2") (pinfunction "2_2") (pintype "passive"))
      (node (ref "C16") (pin "2") (pinfunction "2_2") (pintype "passive"))
      (node (ref "C1A1") (pin "-") (pinfunction "-_-") (pintype "passive"))
      (node (ref "C1A2") (pin "-") (pinfunction "-_-") (pintype "passive"))
      (node (ref "C1B1") (pin "-") (pinfunction "-_-") (pintype "passive"))
      (node (ref "C1B2") (pin "-") (pinfunction "-_-") (pintype "passive"))
      (node (ref "C2") (pin "1") (pinfunction "1_1") (pintype "passive"))
      (node (ref "C3") (pin "-") (pinfunction "-_-") (pintype "passive"))
      (node (ref "C4") (pin "-") (pinfunction "-_-") (pintype "passive"))
      (node (ref "C5") (pin "-") (pinfunction "-_-") (pintype "passive"))
      (node (ref "C6") (pin "1") (pinfunction "1_1") (pintype "passive"))
      (node (ref "C7") (pin "-") (pinfunction "-_-") (pintype "passive"))
      (node (ref "C8") (pin "-") (pinfunction "-_-") (pintype "passive"))
      (node (ref "C9") (pin "-") (pinfunction "-_-") (pintype "passive"))
      (node (ref "D10") (pin "A") (pinfunction "A_A") (pintype "passive"))
      (node (ref "D17") (pin "A") (pinfunction "A_A") (pintype "passive"))
      (node (ref "D18") (pin "A") (pinfunction "A_A") (pintype "passive"))
      (node (ref "D19") (pin "A") (pinfunction "A_A") (pintype "passive"))
      (node (ref "D20") (pin "A") (pinfunction "A_A") (pintype "passive"))
      (node (ref "D22") (pin "A") (pinfunction "A_A") (pintype "passive"))
      (node (ref "D24") (pin "A") (pinfunction "A_A") (pintype "passive"))
      (node (ref "D26") (pin "A") (pinfunction "A_A") (pintype "passive"))
      (node (ref "D28") (pin "A") (pinfunction "A_A") (pintype "passive"))
      (node (ref "D4") (pin "A") (pinfunction "A_A") (pintype "passive"))
      (node (ref "D6") (pin "A") (pinfunction "A_A") (pintype "passive"))
      (node (ref "D8") (pin "A") (pinfunction "A_A") (pintype "passive"))
      (node (ref "IC2") (pin "8") (pinfunction "GND_8") (pintype "power_in"))
      (node (ref "IC4") (pin "8") (pinfunction "GND_8") (pintype "power_in"))
      (node (ref "IC5") (pin "8") (pinfunction "GND_8") (pintype "power_in"))
      (node (ref "J1") (pin "4") (pinfunction "4_4") (pintype "passive"))
      (node (ref "J2") (pin "2") (pinfunction "2_2") (pintype "power_in"))
      (node (ref "J3") (pin "1") (pinfunction "1_1") (pintype "power_in"))
      (node (ref "J5") (pin "4") (pinfunction "4_4") (pintype "passive"))
      (node (ref "J6") (pin "4") (pinfunction "4_4") (pintype "passive"))
      (node (ref "J7") (pin "4") (pinfunction "4_4") (pintype "passive"))
      (node (ref "J8") (pin "GND") (pinfunction "GND_GND") (pintype "bidirectional"))
      (node (ref "J8") (pin "GNDBREAK") (pinfunction "GNDBREAK_GNDBREAK") (pintype "bidirectional"))
      (node (ref "JP1") (pin "1") (pinfunction "1_1") (pintype "passive"))
      (node (ref "JP2") (pin "1") (pinfunction "1_1") (pintype "passive"))
      (node (ref "JP3") (pin "1") (pinfunction "1_1") (pintype "passive"))
      (node (ref "JP5") (pin "3") (pinfunction "3_3") (pintype "passive"))
      (node (ref "JP7") (pin "3") (pinfunction "3_3") (pintype "passive"))
      (node (ref "JP9") (pin "3") (pinfunction "3_3") (pintype "passive"))
      (node (ref "LED1") (pin "C") (pinfunction "C_C") (pintype "passive"))
      (node (ref "LED10") (pin "C") (pinfunction "C_C") (pintype "passive"))
      (node (ref "LED11") (pin "C") (pinfunction "C_C") (pintype "passive"))
      (node (ref "LED12") (pin "C") (pinfunction "C_C") (pintype "passive"))
      (node (ref "LED13") (pin "C") (pinfunction "C_C") (pintype "passive"))
      (node (ref "LED14") (pin "C") (pinfunction "C_C") (pintype "passive"))
      (node (ref "LED15") (pin "C") (pinfunction "C_C") (pintype "passive"))
      (node (ref "LED16") (pin "C") (pinfunction "C_C") (pintype "passive"))
      (node (ref "LED2") (pin "C") (pinfunction "C_C") (pintype "passive"))
      (node (ref "LED3") (pin "C") (pinfunction "C_C") (pintype "passive"))
      (node (ref "LED4") (pin "C") (pinfunction "C_C") (pintype "passive"))
      (node (ref "LED5") (pin "C") (pinfunction "C_C") (pintype "passive"))
      (node (ref "LED6") (pin "C") (pinfunction "C_C") (pintype "passive"))
      (node (ref "LED7") (pin "C") (pinfunction "C_C") (pintype "passive"))
      (node (ref "LED8") (pin "C") (pinfunction "C_C") (pintype "passive"))
      (node (ref "LED9") (pin "C") (pinfunction "C_C") (pintype "passive"))
      (node (ref "PS1") (pin "1") (pinfunction "-VIN_1") (pintype "input"))
      (node (ref "PS2") (pin "1") (pinfunction "-VIN_1") (pintype "input"))
      (node (ref "PS3") (pin "1") (pinfunction "-VIN_1") (pintype "input"))
      (node (ref "PS4") (pin "1") (pinfunction "-VIN_1") (pintype "input"))
      (node (ref "R1") (pin "1") (pinfunction "1_1") (pintype "passive"))
      (node (ref "R10") (pin "1") (pinfunction "1_1") (pintype "passive"))
      (node (ref "R11") (pin "1") (pinfunction "1_1") (pintype "passive"))
      (node (ref "R2A1") (pin "1") (pinfunction "1_1") (pintype "passive"))
      (node (ref "R2A2") (pin "1") (pinfunction "1_1") (pintype "passive"))
      (node (ref "R2B1") (pin "2") (pinfunction "2_2") (pintype "passive"))
      (node (ref "R2B2") (pin "2") (pinfunction "2_2") (pintype "passive"))
      (node (ref "R4") (pin "1") (pinfunction "1_1") (pintype "passive"))
      (node (ref "R5") (pin "1") (pinfunction "1_1") (pintype "passive"))
      (node (ref "R5A1") (pin "2") (pinfunction "2_2") (pintype "passive"))
      (node (ref "R5A2") (pin "2") (pinfunction "2_2") (pintype "passive"))
      (node (ref "R5B1") (pin "2") (pinfunction "2_2") (pintype "passive"))
      (node (ref "R5B2") (pin "2") (pinfunction "2_2") (pintype "passive"))
      (node (ref "R6") (pin "1") (pinfunction "1_1") (pintype "passive"))
      (node (ref "R8") (pin "1") (pinfunction "1_1") (pintype "passive"))
      (node (ref "R9") (pin "1") (pinfunction "1_1") (pintype "passive"))
      (node (ref "U1") (pin "10") (pinfunction "VSS_10") (pintype "power_in"))
      (node (ref "U2") (pin "4") (pinfunction "P$V-_4") (pintype "bidirectional"))
      (node (ref "U3") (pin "4") (pinfunction "P$V-_4") (pintype "bidirectional"))
      (node (ref "X10") (pin "4") (pinfunction "GND1_4") (pintype "power_in"))
      (node (ref "X12") (pin "4") (pinfunction "GND1_4") (pintype "power_in"))
      (node (ref "X13") (pin "2") (pinfunction "2_2") (pintype "passive"))
      (node (ref "X15") (pin "4") (pinfunction "GND1_4") (pintype "power_in"))
      (node (ref "X16") (pin "2") (pinfunction "2_2") (pintype "passive"))
      (node (ref "X22") (pin "1") (pinfunction "S_1") (pintype "passive"))
      (node (ref "X4") (pin "2") (pinfunction "S_2") (pintype "passive"))
      (node (ref "X5") (pin "2") (pinfunction "S_2") (pintype "passive"))
      (node (ref "X6") (pin "2") (pinfunction "S_2") (pintype "passive"))
      (node (ref "X7") (pin "2") (pinfunction "S_2") (pintype "passive"))
      (node (ref "X8") (pin "4") (pinfunction "GND1_4") (pintype "power_in"))
      (node (ref "X9") (pin "2") (pinfunction "2_2") (pintype "passive"))
    )
    (net (code "43") (name "Net-(C1A1-Pad+)") (class "Default")
      (node (ref "C1A1") (pin "+") (pinfunction "+_+") (pintype "passive"))
      (node (ref "R1A1") (pin "1") (pinfunction "1_1") (pintype "passive"))
      (node (ref "R4A2") (pin "1") (pinfunction "1_1") (pintype "passive"))
    )
    (net (code "44") (name "Net-(C1A2-Pad+)") (class "Default")
      (node (ref "C1A2") (pin "+") (pinfunction "+_+") (pintype "passive"))
      (node (ref "R1A2") (pin "1") (pinfunction "1_1") (pintype "passive"))
      (node (ref "R4A1") (pin "1") (pinfunction "1_1") (pintype "passive"))
    )
    (net (code "45") (name "Net-(C1B1-Pad+)") (class "Default")
      (node (ref "C1B1") (pin "+") (pinfunction "+_+") (pintype "passive"))
      (node (ref "R1B1") (pin "2") (pinfunction "2_2") (pintype "passive"))
      (node (ref "R4B1") (pin "1") (pinfunction "1_1") (pintype "passive"))
    )
    (net (code "46") (name "Net-(C1B2-Pad+)") (class "Default")
      (node (ref "C1B2") (pin "+") (pinfunction "+_+") (pintype "passive"))
      (node (ref "R1B2") (pin "2") (pinfunction "2_2") (pintype "passive"))
      (node (ref "R4B2") (pin "1") (pinfunction "1_1") (pintype "passive"))
    )
    (net (code "47") (name "Net-(IC1-ADJ)") (class "Default")
      (node (ref "C4") (pin "+") (pinfunction "+_+") (pintype "passive"))
      (node (ref "D1") (pin "A") (pinfunction "A_A") (pintype "passive"))
      (node (ref "IC1") (pin "1") (pinfunction "ADJ_1") (pintype "input"))
      (node (ref "R2") (pin "1") (pinfunction "1_1") (pintype "passive"))
      (node (ref "R4") (pin "2") (pinfunction "2_2") (pintype "passive"))
    )
    (net (code "48") (name "Net-(IC2-OUT1)") (class "Default")
      (node (ref "D3") (pin "A") (pinfunction "A_A") (pintype "passive"))
      (node (ref "D4") (pin "C") (pinfunction "C_C") (pintype "passive"))
      (node (ref "IC2") (pin "2") (pinfunction "OUT1_2") (pintype "output"))
      (node (ref "R15") (pin "1") (pinfunction "1_1") (pintype "passive"))
      (node (ref "X9") (pin "1") (pinfunction "1_1") (pintype "passive"))
    )
    (net (code "49") (name "Net-(IC2-OUT2)") (class "Default")
      (node (ref "D5") (pin "A") (pinfunction "A_A") (pintype "passive"))
      (node (ref "D6") (pin "C") (pinfunction "C_C") (pintype "passive"))
      (node (ref "IC2") (pin "3") (pinfunction "OUT2_3") (pintype "output"))
      (node (ref "R15") (pin "2") (pinfunction "1_2") (pintype "passive"))
      (node (ref "X9") (pin "3") (pinfunction "3_3") (pintype "passive"))
    )
    (net (code "50") (name "Net-(IC2-OUT3)") (class "Default")
      (node (ref "D7") (pin "A") (pinfunction "A_A") (pintype "passive"))
      (node (ref "D8") (pin "C") (pinfunction "C_C") (pintype "passive"))
      (node (ref "IC2") (pin "13") (pinfunction "OUT3_13") (pintype "output"))
      (node (ref "R15") (pin "3") (pinfunction "1_3") (pintype "passive"))
      (node (ref "X9") (pin "5") (pinfunction "5_5") (pintype "passive"))
    )
    (net (code "51") (name "Net-(IC2-OUT4)") (class "Default")
      (node (ref "D10") (pin "C") (pinfunction "C_C") (pintype "passive"))
      (node (ref "D9") (pin "A") (pinfunction "A_A") (pintype "passive"))
      (node (ref "IC2") (pin "14") (pinfunction "OUT4_14") (pintype "output"))
      (node (ref "R15") (pin "4") (pinfunction "1_4") (pintype "passive"))
      (node (ref "X9") (pin "7") (pinfunction "7_7") (pintype "passive"))
    )
    (net (code "52") (name "Net-(IC2-SEN_A)") (class "Default")
      (node (ref "IC2") (pin "1") (pinfunction "SEN_A_1") (pintype "input"))
      (node (ref "R1") (pin "2") (pinfunction "2_2") (pintype "passive"))
    )
    (net (code "53") (name "Net-(IC2-SEN_B)") (class "Default")
      (node (ref "IC2") (pin "15") (pinfunction "SEN_B_15") (pintype "input"))
      (node (ref "R6") (pin "2") (pinfunction "2_2") (pintype "passive"))
    )
    (net (code "54") (name "Net-(IC3-ADJ)") (class "Default")
      (node (ref "C8") (pin "+") (pinfunction "+_+") (pintype "passive"))
      (node (ref "D11") (pin "A") (pinfunction "A_A") (pintype "passive"))
      (node (ref "IC3") (pin "1") (pinfunction "ADJ_1") (pintype "input"))
      (node (ref "R3") (pin "1") (pinfunction "1_1") (pintype "passive"))
      (node (ref "R5") (pin "2") (pinfunction "2_2") (pintype "passive"))
    )
    (net (code "55") (name "Net-(IC4-OUT1)") (class "Default")
      (node (ref "D13") (pin "A") (pinfunction "A_A") (pintype "passive"))
      (node (ref "D17") (pin "C") (pinfunction "C_C") (pintype "passive"))
      (node (ref "IC4") (pin "2") (pinfunction "OUT1_2") (pintype "output"))
      (node (ref "R19") (pin "1") (pinfunction "1_1") (pintype "passive"))
      (node (ref "X13") (pin "1") (pinfunction "1_1") (pintype "passive"))
    )
    (net (code "56") (name "Net-(IC4-OUT2)") (class "Default")
      (node (ref "D14") (pin "A") (pinfunction "A_A") (pintype "passive"))
      (node (ref "D18") (pin "C") (pinfunction "C_C") (pintype "passive"))
      (node (ref "IC4") (pin "3") (pinfunction "OUT2_3") (pintype "output"))
      (node (ref "R19") (pin "2") (pinfunction "1_2") (pintype "passive"))
      (node (ref "X13") (pin "3") (pinfunction "3_3") (pintype "passive"))
    )
    (net (code "57") (name "Net-(IC4-OUT3)") (class "Default")
      (node (ref "D15") (pin "A") (pinfunction "A_A") (pintype "passive"))
      (node (ref "D19") (pin "C") (pinfunction "C_C") (pintype "passive"))
      (node (ref "IC4") (pin "13") (pinfunction "OUT3_13") (pintype "output"))
      (node (ref "R19") (pin "3") (pinfunction "1_3") (pintype "passive"))
      (node (ref "X13") (pin "5") (pinfunction "5_5") (pintype "passive"))
    )
    (net (code "58") (name "Net-(IC4-OUT4)") (class "Default")
      (node (ref "D16") (pin "A") (pinfunction "A_A") (pintype "passive"))
      (node (ref "D20") (pin "C") (pinfunction "C_C") (pintype "passive"))
      (node (ref "IC4") (pin "14") (pinfunction "OUT4_14") (pintype "output"))
      (node (ref "R19") (pin "4") (pinfunction "1_4") (pintype "passive"))
      (node (ref "X13") (pin "7") (pinfunction "7_7") (pintype "passive"))
    )
    (net (code "59") (name "Net-(IC4-SEN_A)") (class "Default")
      (node (ref "IC4") (pin "1") (pinfunction "SEN_A_1") (pintype "input"))
      (node (ref "R9") (pin "2") (pinfunction "2_2") (pintype "passive"))
    )
    (net (code "60") (name "Net-(IC4-SEN_B)") (class "Default")
      (node (ref "IC4") (pin "15") (pinfunction "SEN_B_15") (pintype "input"))
      (node (ref "R8") (pin "2") (pinfunction "2_2") (pintype "passive"))
    )
    (net (code "61") (name "Net-(IC5-OUT1)") (class "Default")
      (node (ref "D21") (pin "A") (pinfunction "A_A") (pintype "passive"))
      (node (ref "D22") (pin "C") (pinfunction "C_C") (pintype "passive"))
      (node (ref "IC5") (pin "2") (pinfunction "OUT1_2") (pintype "output"))
      (node (ref "R22") (pin "1") (pinfunction "1_1") (pintype "passive"))
      (node (ref "X16") (pin "1") (pinfunction "1_1") (pintype "passive"))
    )
    (net (code "62") (name "Net-(IC5-OUT2)") (class "Default")
      (node (ref "D23") (pin "A") (pinfunction "A_A") (pintype "passive"))
      (node (ref "D24") (pin "C") (pinfunction "C_C") (pintype "passive"))
      (node (ref "IC5") (pin "3") (pinfunction "OUT2_3") (pintype "output"))
      (node (ref "R22") (pin "2") (pinfunction "1_2") (pintype "passive"))
      (node (ref "X16") (pin "3") (pinfunction "3_3") (pintype "passive"))
    )
    (net (code "63") (name "Net-(IC5-OUT3)") (class "Default")
      (node (ref "D25") (pin "A") (pinfunction "A_A") (pintype "passive"))
      (node (ref "D26") (pin "C") (pinfunction "C_C") (pintype "passive"))
      (node (ref "IC5") (pin "13") (pinfunction "OUT3_13") (pintype "output"))
      (node (ref "R22") (pin "3") (pinfunction "1_3") (pintype "passive"))
      (node (ref "X16") (pin "5") (pinfunction "5_5") (pintype "passive"))
    )
    (net (code "64") (name "Net-(IC5-OUT4)") (class "Default")
      (node (ref "D27") (pin "A") (pinfunction "A_A") (pintype "passive"))
      (node (ref "D28") (pin "C") (pinfunction "C_C") (pintype "passive"))
      (node (ref "IC5") (pin "14") (pinfunction "OUT4_14") (pintype "output"))
      (node (ref "R22") (pin "4") (pinfunction "1_4") (pintype "passive"))
      (node (ref "X16") (pin "7") (pinfunction "7_7") (pintype "passive"))
    )
    (net (code "65") (name "Net-(IC5-SEN_A)") (class "Default")
      (node (ref "IC5") (pin "1") (pinfunction "SEN_A_1") (pintype "input"))
      (node (ref "R11") (pin "2") (pinfunction "2_2") (pintype "passive"))
    )
    (net (code "66") (name "Net-(IC5-SEN_B)") (class "Default")
      (node (ref "IC5") (pin "15") (pinfunction "SEN_B_15") (pintype "input"))
      (node (ref "R10") (pin "2") (pinfunction "2_2") (pintype "passive"))
    )
    (net (code "67") (name "Net-(JP13-Pad2)") (class "Default")
      (node (ref "JP13") (pin "2") (pinfunction "2_2") (pintype "passive"))
      (node (ref "X18") (pin "1") (pinfunction "1_1") (pintype "passive"))
    )
    (net (code "68") (name "Net-(JP13-Pad3)") (class "Default")
      (node (ref "JP13") (pin "3") (pinfunction "3_3") (pintype "passive"))
      (node (ref "X18") (pin "2") (pinfunction "2_2") (pintype "passive"))
      (node (ref "X18") (pin "3") (pinfunction "2_3") (pintype "passive"))
      (node (ref "X18") (pin "4") (pinfunction "2_4") (pintype "passive"))
      (node (ref "X18") (pin "5") (pinfunction "2_5") (pintype "passive"))
    )
    (net (code "69") (name "Net-(JP15-Pad2)") (class "Default")
      (node (ref "JP15") (pin "2") (pinfunction "2_2") (pintype "passive"))
      (node (ref "X19") (pin "1") (pinfunction "1_1") (pintype "passive"))
    )
    (net (code "70") (name "Net-(JP15-Pad3)") (class "Default")
      (node (ref "JP15") (pin "3") (pinfunction "3_3") (pintype "passive"))
      (node (ref "X19") (pin "2") (pinfunction "2_2") (pintype "passive"))
      (node (ref "X19") (pin "3") (pinfunction "2_3") (pintype "passive"))
      (node (ref "X19") (pin "4") (pinfunction "2_4") (pintype "passive"))
      (node (ref "X19") (pin "5") (pinfunction "2_5") (pintype "passive"))
    )
    (net (code "71") (name "Net-(JP17-Pad2)") (class "Default")
      (node (ref "JP17") (pin "2") (pinfunction "2_2") (pintype "passive"))
      (node (ref "X20") (pin "1") (pinfunction "1_1") (pintype "passive"))
    )
    (net (code "72") (name "Net-(JP17-Pad3)") (class "Default")
      (node (ref "JP17") (pin "3") (pinfunction "3_3") (pintype "passive"))
      (node (ref "X20") (pin "2") (pinfunction "2_2") (pintype "passive"))
      (node (ref "X20") (pin "3") (pinfunction "2_3") (pintype "passive"))
      (node (ref "X20") (pin "4") (pinfunction "2_4") (pintype "passive"))
      (node (ref "X20") (pin "5") (pinfunction "2_5") (pintype "passive"))
    )
    (net (code "73") (name "Net-(JP19-Pad2)") (class "Default")
      (node (ref "JP19") (pin "2") (pinfunction "2_2") (pintype "passive"))
      (node (ref "X21") (pin "1") (pinfunction "1_1") (pintype "passive"))
    )
    (net (code "74") (name "Net-(JP19-Pad3)") (class "Default")
      (node (ref "JP19") (pin "3") (pinfunction "3_3") (pintype "passive"))
      (node (ref "X21") (pin "2") (pinfunction "2_2") (pintype "passive"))
      (node (ref "X21") (pin "3") (pinfunction "2_3") (pintype "passive"))
      (node (ref "X21") (pin "4") (pinfunction "2_4") (pintype "passive"))
      (node (ref "X21") (pin "5") (pinfunction "2_5") (pintype "passive"))
    )
    (net (code "75") (name "Net-(R3-1A1-CCW)") (class "Default")
      (node (ref "R2A1") (pin "2") (pinfunction "2_2") (pintype "passive"))
      (node (ref "R3-1A1") (pin "1") (pinfunction "CCW_1") (pintype "passive"))
      (node (ref "U2") (pin "6") (pinfunction "-IN_6") (pintype "input"))
    )
    (net (code "76") (name "Net-(R3-1A1-CW)") (class "Default")
      (node (ref "R3-1A1") (pin "2") (pinfunction "WIPER_2") (pintype "passive"))
      (node (ref "R3-1A1") (pin "3") (pinfunction "CW_3") (pintype "passive"))
      (node (ref "R3-2A1") (pin "1") (pinfunction "1_1") (pintype "passive"))
    )
    (net (code "77") (name "Net-(R3-1A2-CCW)") (class "Default")
      (node (ref "R2A2") (pin "2") (pinfunction "2_2") (pintype "passive"))
      (node (ref "R3-1A2") (pin "1") (pinfunction "CCW_1") (pintype "passive"))
      (node (ref "U3") (pin "6") (pinfunction "-IN_6") (pintype "input"))
    )
    (net (code "78") (name "Net-(R3-1A2-CW)") (class "Default")
      (node (ref "R3-1A2") (pin "2") (pinfunction "WIPER_2") (pintype "passive"))
      (node (ref "R3-1A2") (pin "3") (pinfunction "CW_3") (pintype "passive"))
      (node (ref "R3-2A2") (pin "1") (pinfunction "1_1") (pintype "passive"))
    )
    (net (code "79") (name "Net-(R3-1B1-CCW)") (class "Default")
      (node (ref "R2B1") (pin "1") (pinfunction "1_1") (pintype "passive"))
      (node (ref "R3-1B1") (pin "1") (pinfunction "CCW_1") (pintype "passive"))
      (node (ref "U2") (pin "2") (pinfunction "-IN_2") (pintype "input"))
    )
    (net (code "80") (name "Net-(R3-1B1-CW)") (class "Default")
      (node (ref "R3-1B1") (pin "2") (pinfunction "WIPER_2") (pintype "passive"))
      (node (ref "R3-1B1") (pin "3") (pinfunction "CW_3") (pintype "passive"))
      (node (ref "R3-2B1") (pin "1") (pinfunction "1_1") (pintype "passive"))
    )
    (net (code "81") (name "Net-(R3-1B2-CCW)") (class "Default")
      (node (ref "R2B2") (pin "1") (pinfunction "1_1") (pintype "passive"))
      (node (ref "R3-1B2") (pin "1") (pinfunction "CCW_1") (pintype "passive"))
      (node (ref "U3") (pin "2") (pinfunction "-IN_2") (pintype "input"))
    )
    (net (code "82") (name "Net-(R3-1B2-CW)") (class "Default")
      (node (ref "R3-1B2") (pin "2") (pinfunction "WIPER_2") (pintype "passive"))
      (node (ref "R3-1B2") (pin "3") (pinfunction "CW_3") (pintype "passive"))
      (node (ref "R3-2B2") (pin "1") (pinfunction "1_1") (pintype "passive"))
    )
    (net (code "83") (name "Net-(R3-2A1-Pad2)") (class "Default")
      (node (ref "R3-2A1") (pin "2") (pinfunction "2_2") (pintype "passive"))
      (node (ref "R3-3A1") (pin "1") (pinfunction "1_1") (pintype "passive"))
    )
    (net (code "84") (name "Net-(R3-2A2-Pad2)") (class "Default")
      (node (ref "R3-2A2") (pin "2") (pinfunction "2_2") (pintype "passive"))
      (node (ref "R3-3A2") (pin "1") (pinfunction "1_1") (pintype "passive"))
    )
    (net (code "85") (name "Net-(R3-2B1-Pad2)") (class "Default")
      (node (ref "R3-2B1") (pin "2") (pinfunction "2_2") (pintype "passive"))
      (node (ref "R3-3B1") (pin "1") (pinfunction "1_1") (pintype "passive"))
    )
    (net (code "86") (name "Net-(R3-2B2-Pad2)") (class "Default")
      (node (ref "R3-2B2") (pin "2") (pinfunction "2_2") (pintype "passive"))
      (node (ref "R3-3B2") (pin "1") (pinfunction "1_1") (pintype "passive"))
    )
    (net (code "87") (name "Net-(R7A-2)") (class "Default")
      (node (ref "LED1") (pin "A") (pinfunction "A_A") (pintype "passive"))
      (node (ref "R7") (pin "8") (pinfunction "2_8") (pintype "passive"))
    )
    (net (code "88") (name "Net-(R7B-2)") (class "Default")
      (node (ref "LED2") (pin "A") (pinfunction "A_A") (pintype "passive"))
      (node (ref "R7") (pin "7") (pinfunction "2_7") (pintype "passive"))
    )
    (net (code "89") (name "Net-(R7C-2)") (class "Default")
      (node (ref "LED3") (pin "A") (pinfunction "A_A") (pintype "passive"))
      (node (ref "R7") (pin "6") (pinfunction "2_6") (pintype "passive"))
    )
    (net (code "90") (name "Net-(R7D-2)") (class "Default")
      (node (ref "LED4") (pin "A") (pinfunction "A_A") (pintype "passive"))
      (node (ref "R7") (pin "5") (pinfunction "2_5") (pintype "passive"))
    )
    (net (code "91") (name "Net-(R15A-2)") (class "Default")
      (node (ref "LED5") (pin "A") (pinfunction "A_A") (pintype "passive"))
      (node (ref "R15") (pin "8") (pinfunction "2_8") (pintype "passive"))
    )
    (net (code "92") (name "Net-(R15B-2)") (class "Default")
      (node (ref "LED6") (pin "A") (pinfunction "A_A") (pintype "passive"))
      (node (ref "R15") (pin "7") (pinfunction "2_7") (pintype "passive"))
    )
    (net (code "93") (name "Net-(R15C-2)") (class "Default")
      (node (ref "LED7") (pin "A") (pinfunction "A_A") (pintype "passive"))
      (node (ref "R15") (pin "6") (pinfunction "2_6") (pintype "passive"))
    )
    (net (code "94") (name "Net-(R15D-2)") (class "Default")
      (node (ref "LED8") (pin "A") (pinfunction "A_A") (pintype "passive"))
      (node (ref "R15") (pin "5") (pinfunction "2_5") (pintype "passive"))
    )
    (net (code "95") (name "Net-(R19A-2)") (class "Default")
      (node (ref "LED9") (pin "A") (pinfunction "A_A") (pintype "passive"))
      (node (ref "R19") (pin "8") (pinfunction "2_8") (pintype "passive"))
    )
    (net (code "96") (name "Net-(R19B-2)") (class "Default")
      (node (ref "LED10") (pin "A") (pinfunction "A_A") (pintype "passive"))
      (node (ref "R19") (pin "7") (pinfunction "2_7") (pintype "passive"))
    )
    (net (code "97") (name "Net-(R19C-2)") (class "Default")
      (node (ref "LED11") (pin "A") (pinfunction "A_A") (pintype "passive"))
      (node (ref "R19") (pin "6") (pinfunction "2_6") (pintype "passive"))
    )
    (net (code "98") (name "Net-(R19D-2)") (class "Default")
      (node (ref "LED12") (pin "A") (pinfunction "A_A") (pintype "passive"))
      (node (ref "R19") (pin "5") (pinfunction "2_5") (pintype "passive"))
    )
    (net (code "99") (name "Net-(R22A-2)") (class "Default")
      (node (ref "LED13") (pin "A") (pinfunction "A_A") (pintype "passive"))
      (node (ref "R22") (pin "8") (pinfunction "2_8") (pintype "passive"))
    )
    (net (code "100") (name "Net-(R22B-2)") (class "Default")
      (node (ref "LED14") (pin "A") (pinfunction "A_A") (pintype "passive"))
      (node (ref "R22") (pin "7") (pinfunction "2_7") (pintype "passive"))
    )
    (net (code "101") (name "Net-(R22C-2)") (class "Default")
      (node (ref "LED15") (pin "A") (pinfunction "A_A") (pintype "passive"))
      (node (ref "R22") (pin "6") (pinfunction "2_6") (pintype "passive"))
    )
    (net (code "102") (name "Net-(R22D-2)") (class "Default")
      (node (ref "LED16") (pin "A") (pinfunction "A_A") (pintype "passive"))
      (node (ref "R22") (pin "5") (pinfunction "2_5") (pintype "passive"))
    )
    (net (code "103") (name "Net-(U1-A0)") (class "Default")
      (node (ref "JP1") (pin "2") (pinfunction "2_2") (pintype "passive"))
      (node (ref "U1") (pin "15") (pinfunction "A0_15") (pintype "input"))
    )
    (net (code "104") (name "Net-(U1-A1)") (class "Default")
      (node (ref "JP2") (pin "2") (pinfunction "2_2") (pintype "passive"))
      (node (ref "U1") (pin "16") (pinfunction "A1_16") (pintype "input"))
    )
    (net (code "105") (name "Net-(U1-A2)") (class "Default")
      (node (ref "JP3") (pin "2") (pinfunction "2_2") (pintype "passive"))
      (node (ref "U1") (pin "17") (pinfunction "A2_17") (pintype "input"))
    )
    (net (code "106") (name "Net-(U2A-+IN)") (class "Default")
      (node (ref "R4B1") (pin "2") (pinfunction "2_2") (pintype "passive"))
      (node (ref "U2") (pin "3") (pinfunction "+IN_3") (pintype "input"))
    )
    (net (code "107") (name "Net-(U2A-OUT)") (class "Default")
      (node (ref "R3-3B1") (pin "2") (pinfunction "2_2") (pintype "passive"))
      (node (ref "U2") (pin "1") (pinfunction "OUT_1") (pintype "output"))
      (node (ref "X5") (pin "1") (pinfunction "S_1") (pintype "passive"))
    )
    (net (code "108") (name "Net-(U2B-+IN)") (class "Default")
      (node (ref "R4A2") (pin "2") (pinfunction "2_2") (pintype "passive"))
      (node (ref "U2") (pin "5") (pinfunction "+IN_5") (pintype "input"))
    )
    (net (code "109") (name "Net-(U2B-OUT)") (class "Default")
      (node (ref "R3-3A1") (pin "2") (pinfunction "2_2") (pintype "passive"))
      (node (ref "U2") (pin "7") (pinfunction "OUT_7") (pintype "output"))
      (node (ref "X4") (pin "1") (pinfunction "S_1") (pintype "passive"))
    )
    (net (code "110") (name "Net-(U3A-+IN)") (class "Default")
      (node (ref "R4B2") (pin "2") (pinfunction "2_2") (pintype "passive"))
      (node (ref "U3") (pin "3") (pinfunction "+IN_3") (pintype "input"))
    )
    (net (code "111") (name "Net-(U3A-OUT)") (class "Default")
      (node (ref "R3-3B2") (pin "2") (pinfunction "2_2") (pintype "passive"))
      (node (ref "U3") (pin "1") (pinfunction "OUT_1") (pintype "output"))
      (node (ref "X7") (pin "1") (pinfunction "S_1") (pintype "passive"))
    )
    (net (code "112") (name "Net-(U3B-+IN)") (class "Default")
      (node (ref "R4A1") (pin "2") (pinfunction "2_2") (pintype "passive"))
      (node (ref "U3") (pin "5") (pinfunction "+IN_5") (pintype "input"))
    )
    (net (code "113") (name "Net-(U3B-OUT)") (class "Default")
      (node (ref "R3-3A2") (pin "2") (pinfunction "2_2") (pintype "passive"))
      (node (ref "U3") (pin "7") (pinfunction "OUT_7") (pintype "output"))
      (node (ref "X6") (pin "1") (pinfunction "S_1") (pintype "passive"))
    )
    (net (code "114") (name "Net-(X11A-S)") (class "Default")
      (node (ref "JP6") (pin "3") (pinfunction "3_3") (pintype "passive"))
      (node (ref "X11") (pin "1") (pinfunction "S_1") (pintype "passive"))
    )
    (net (code "115") (name "Net-(X11B-S)") (class "Default")
      (node (ref "JP6") (pin "2") (pinfunction "2_2") (pintype "passive"))
      (node (ref "X11") (pin "2") (pinfunction "S_2") (pintype "passive"))
    )
    (net (code "116") (name "Net-(X14A-S)") (class "Default")
      (node (ref "JP8") (pin "3") (pinfunction "3_3") (pintype "passive"))
      (node (ref "X14") (pin "1") (pinfunction "S_1") (pintype "passive"))
    )
    (net (code "117") (name "Net-(X14B-S)") (class "Default")
      (node (ref "JP8") (pin "2") (pinfunction "2_2") (pintype "passive"))
      (node (ref "X14") (pin "2") (pinfunction "S_2") (pintype "passive"))
    )
    (net (code "118") (name "Net-(X17A-S)") (class "Default")
      (node (ref "JP10") (pin "3") (pinfunction "3_3") (pintype "passive"))
      (node (ref "X17") (pin "1") (pinfunction "S_1") (pintype "passive"))
    )
    (net (code "119") (name "Net-(X17B-S)") (class "Default")
      (node (ref "JP10") (pin "2") (pinfunction "2_2") (pintype "passive"))
      (node (ref "X17") (pin "2") (pinfunction "S_2") (pintype "passive"))
    )
    (net (code "120") (name "unconnected-(U1-INTA-Pad20)") (class "Default")
      (node (ref "U1") (pin "20") (pinfunction "INTA_20") (pintype "output"))
    )
    (net (code "121") (name "unconnected-(U1-INTB-Pad19)") (class "Default")
      (node (ref "U1") (pin "19") (pinfunction "INTB_19") (pintype "output"))
    )
  )
)
